# cd32_breakout_1_1a.net
KiCad netlist of a schematic drawn in EAGLE
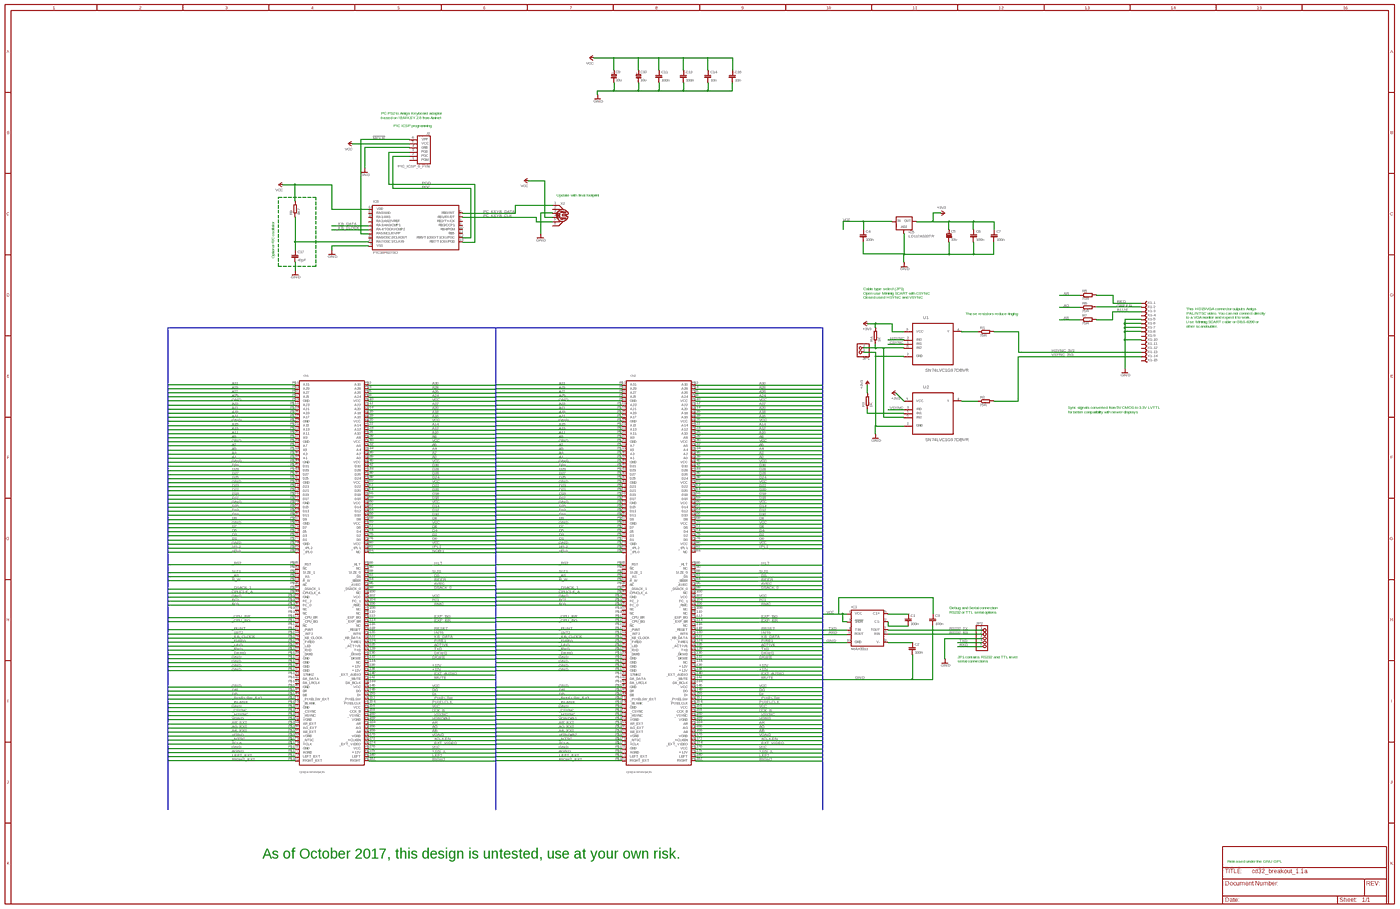
[diagram p0: schematic, sheet 1, overview]
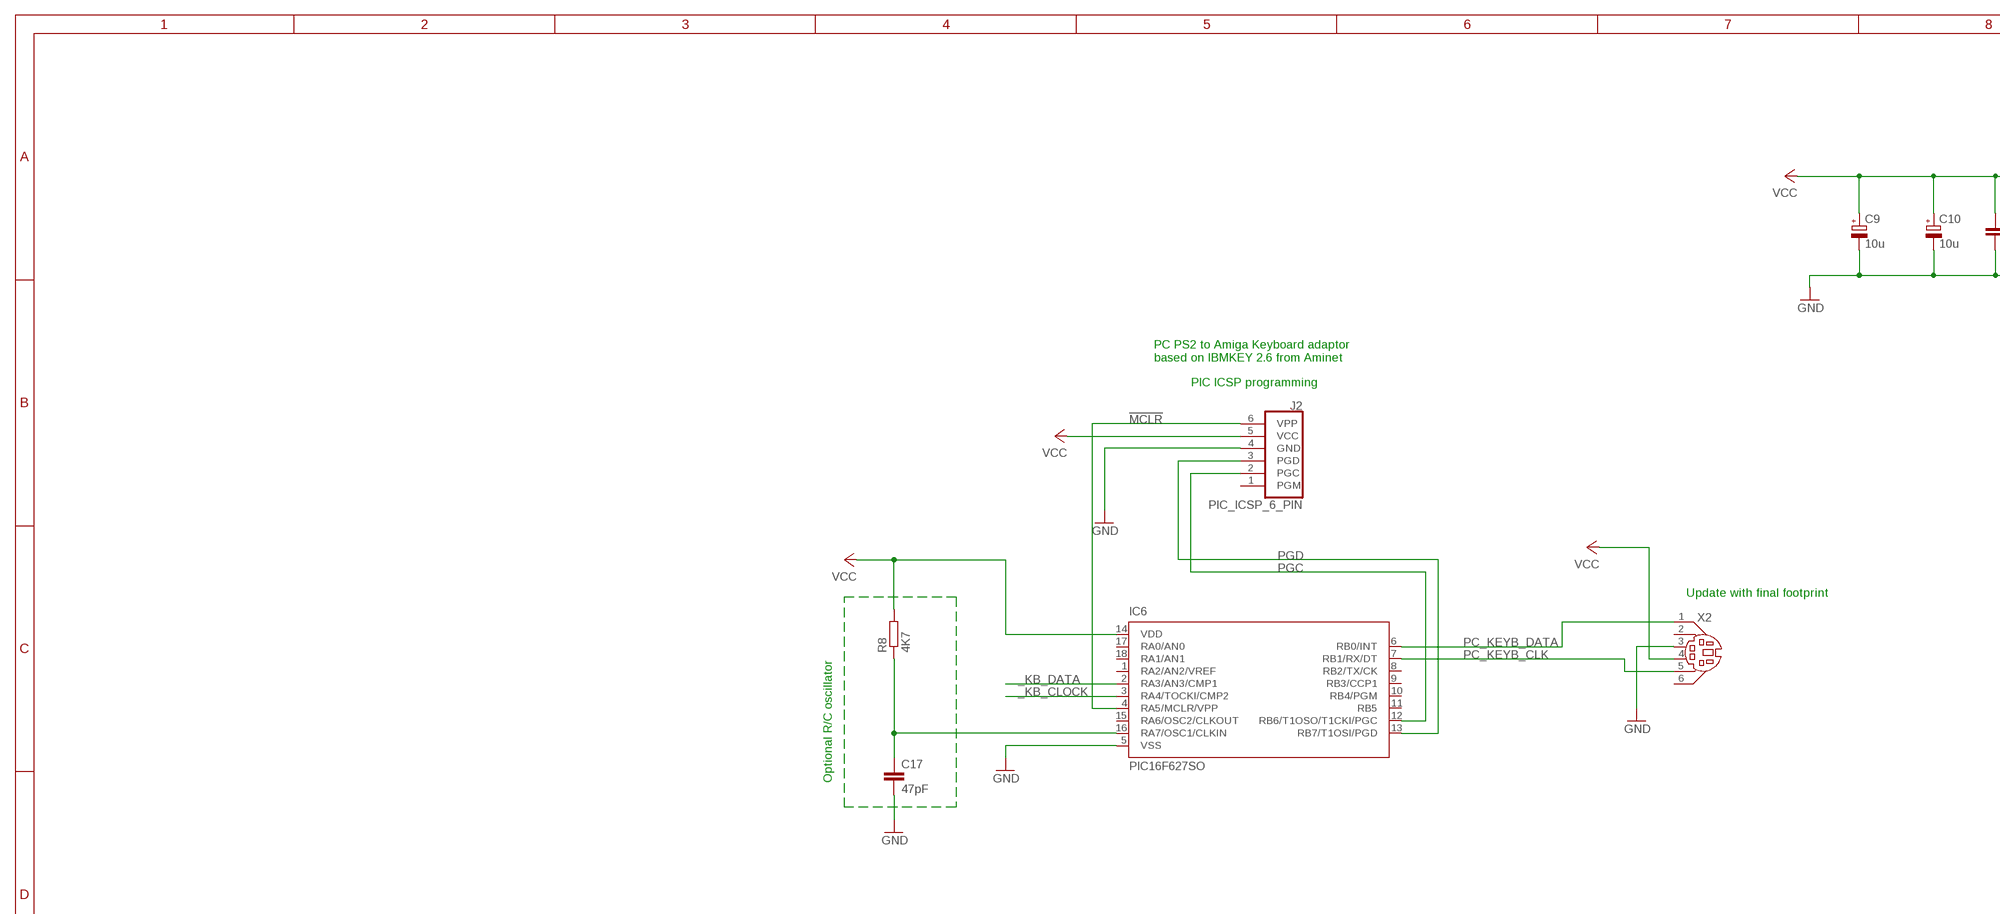
[diagram p1: schematic, sheet 1, part 1 of 4]
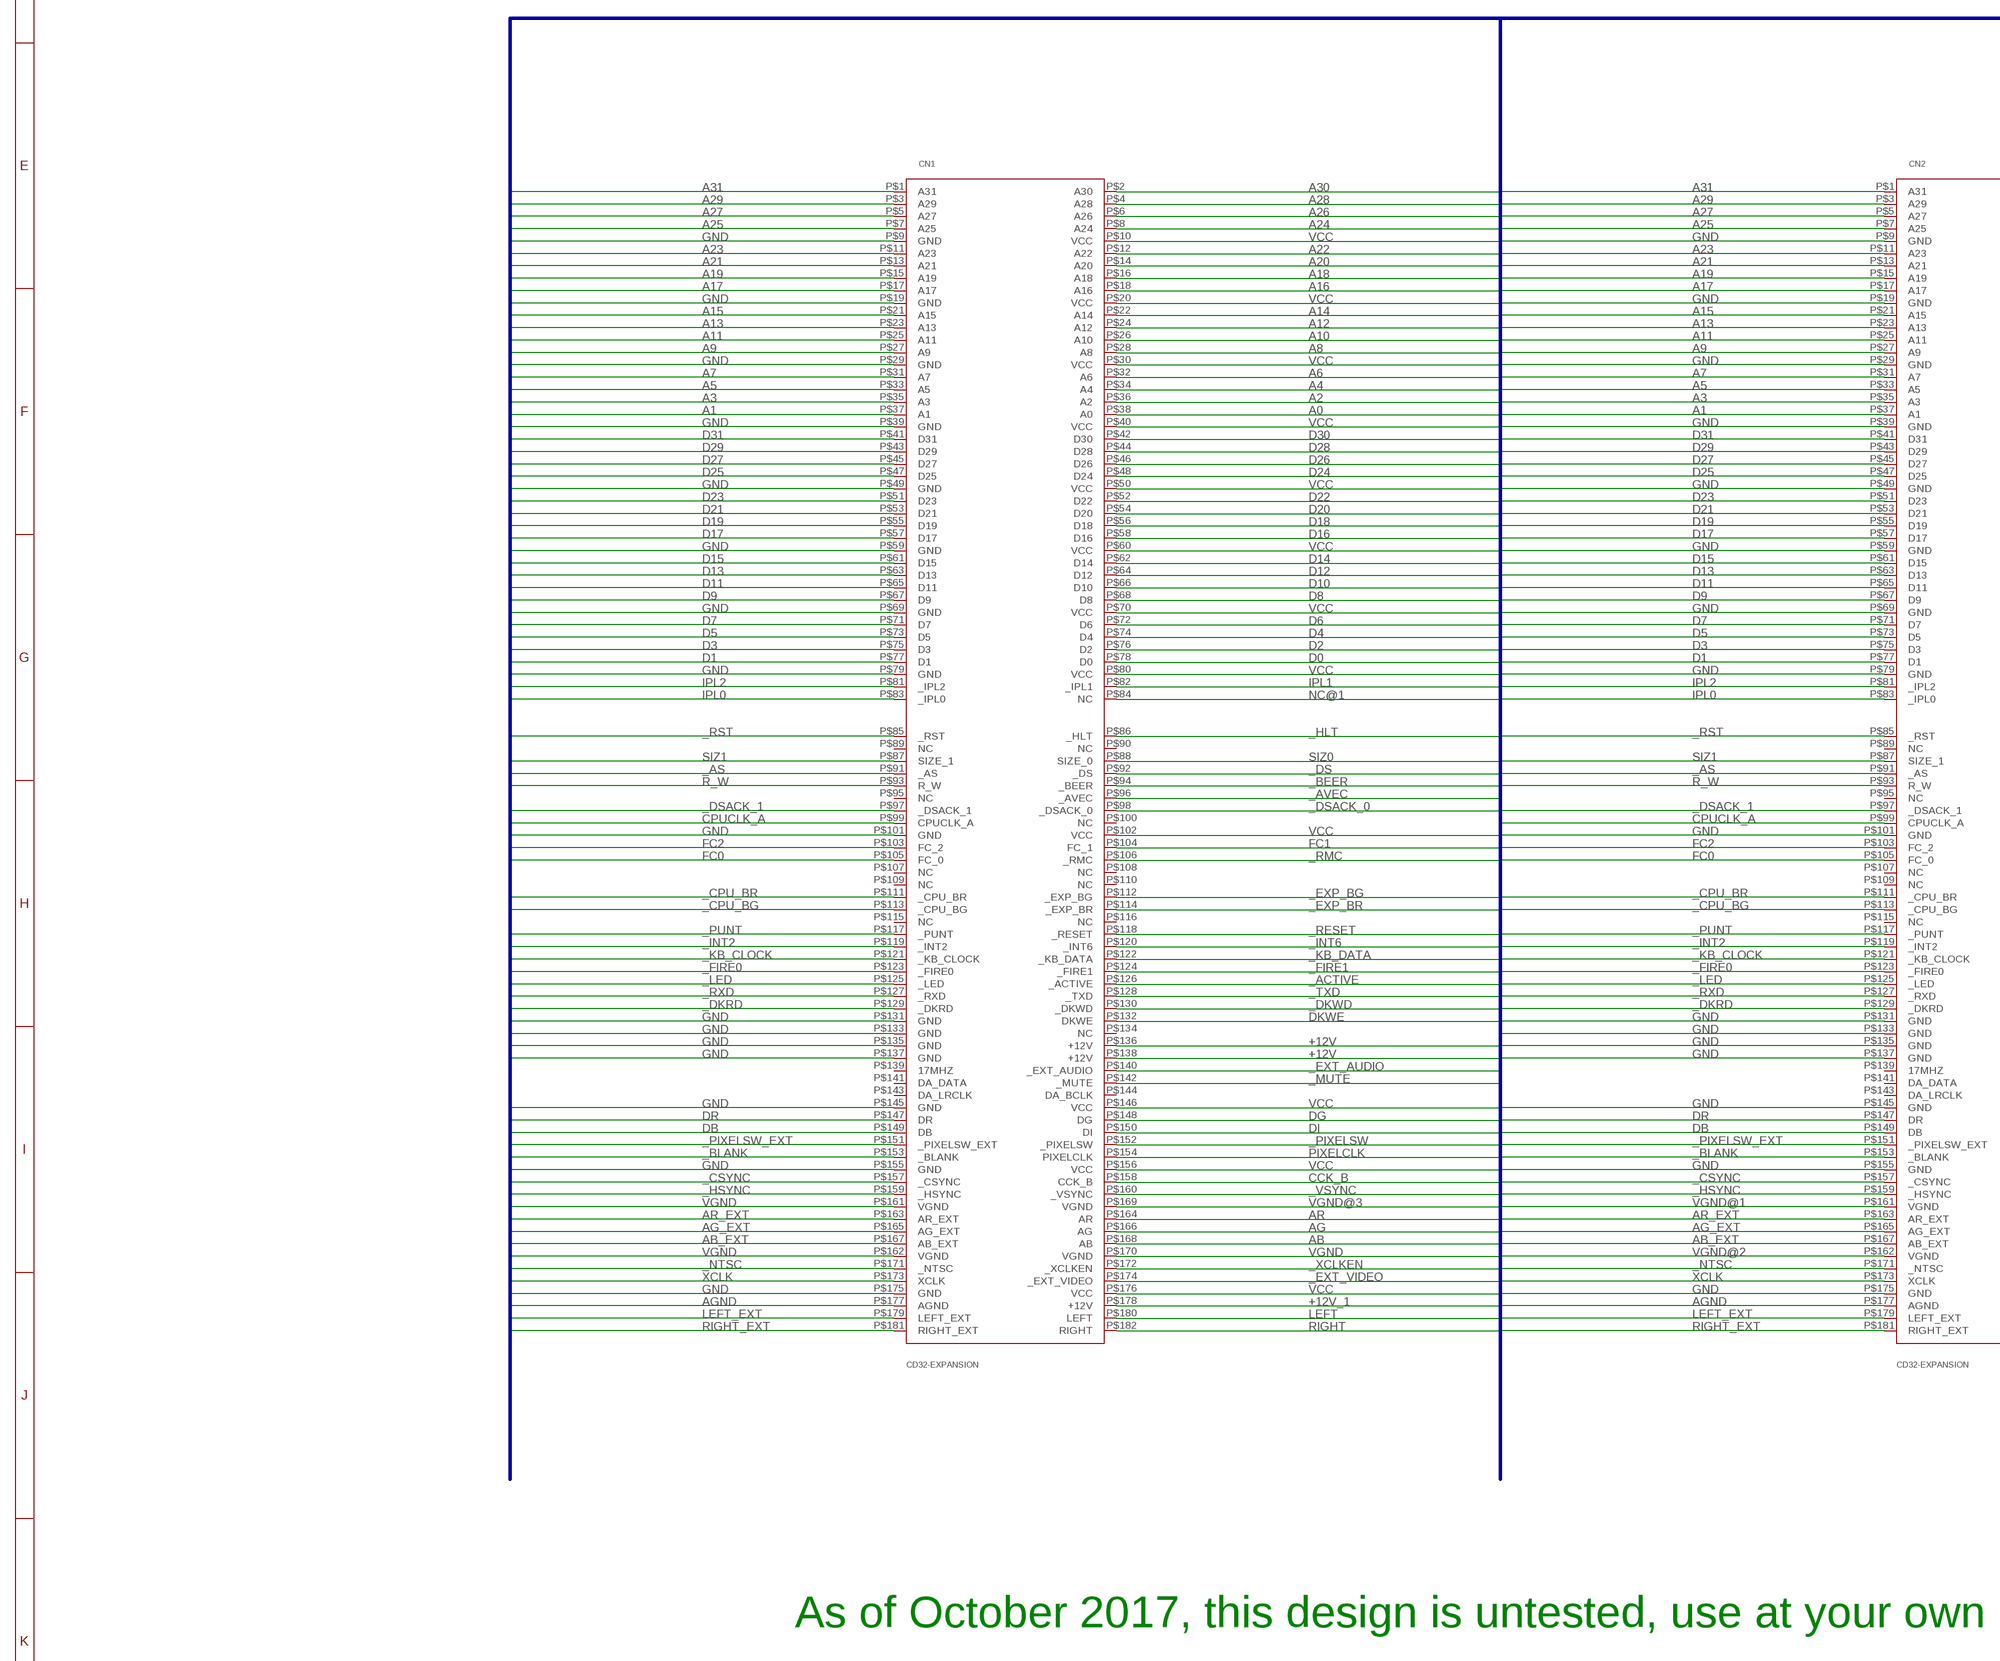
[diagram p2: schematic, sheet 1, part 2 of 4]
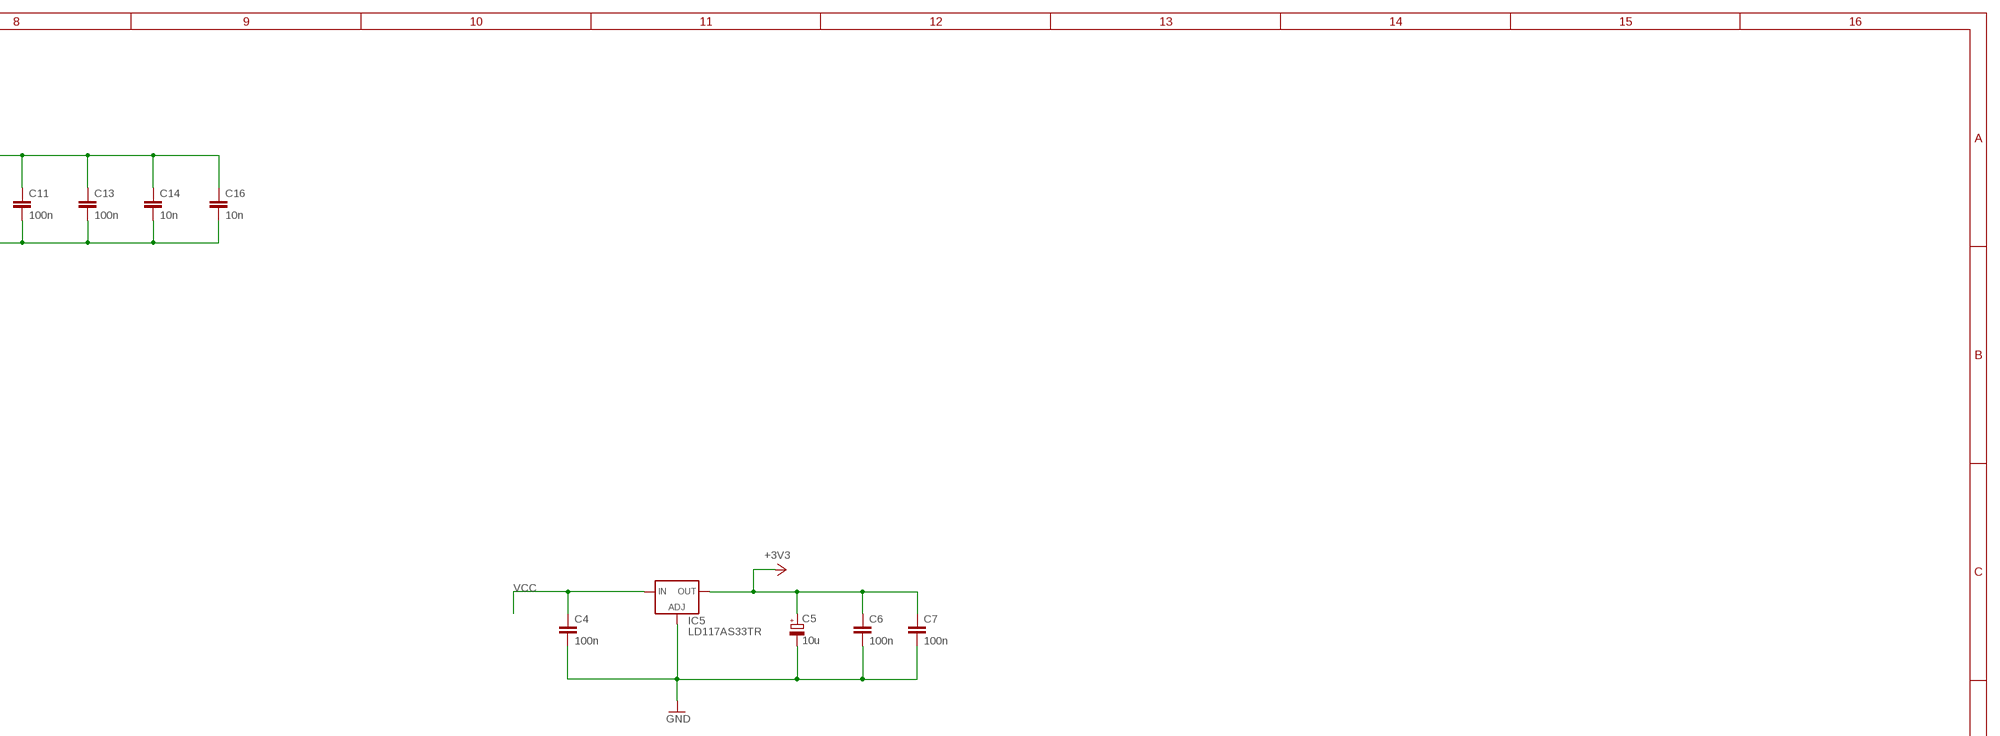
[diagram p3: schematic, sheet 1, part 3 of 4]
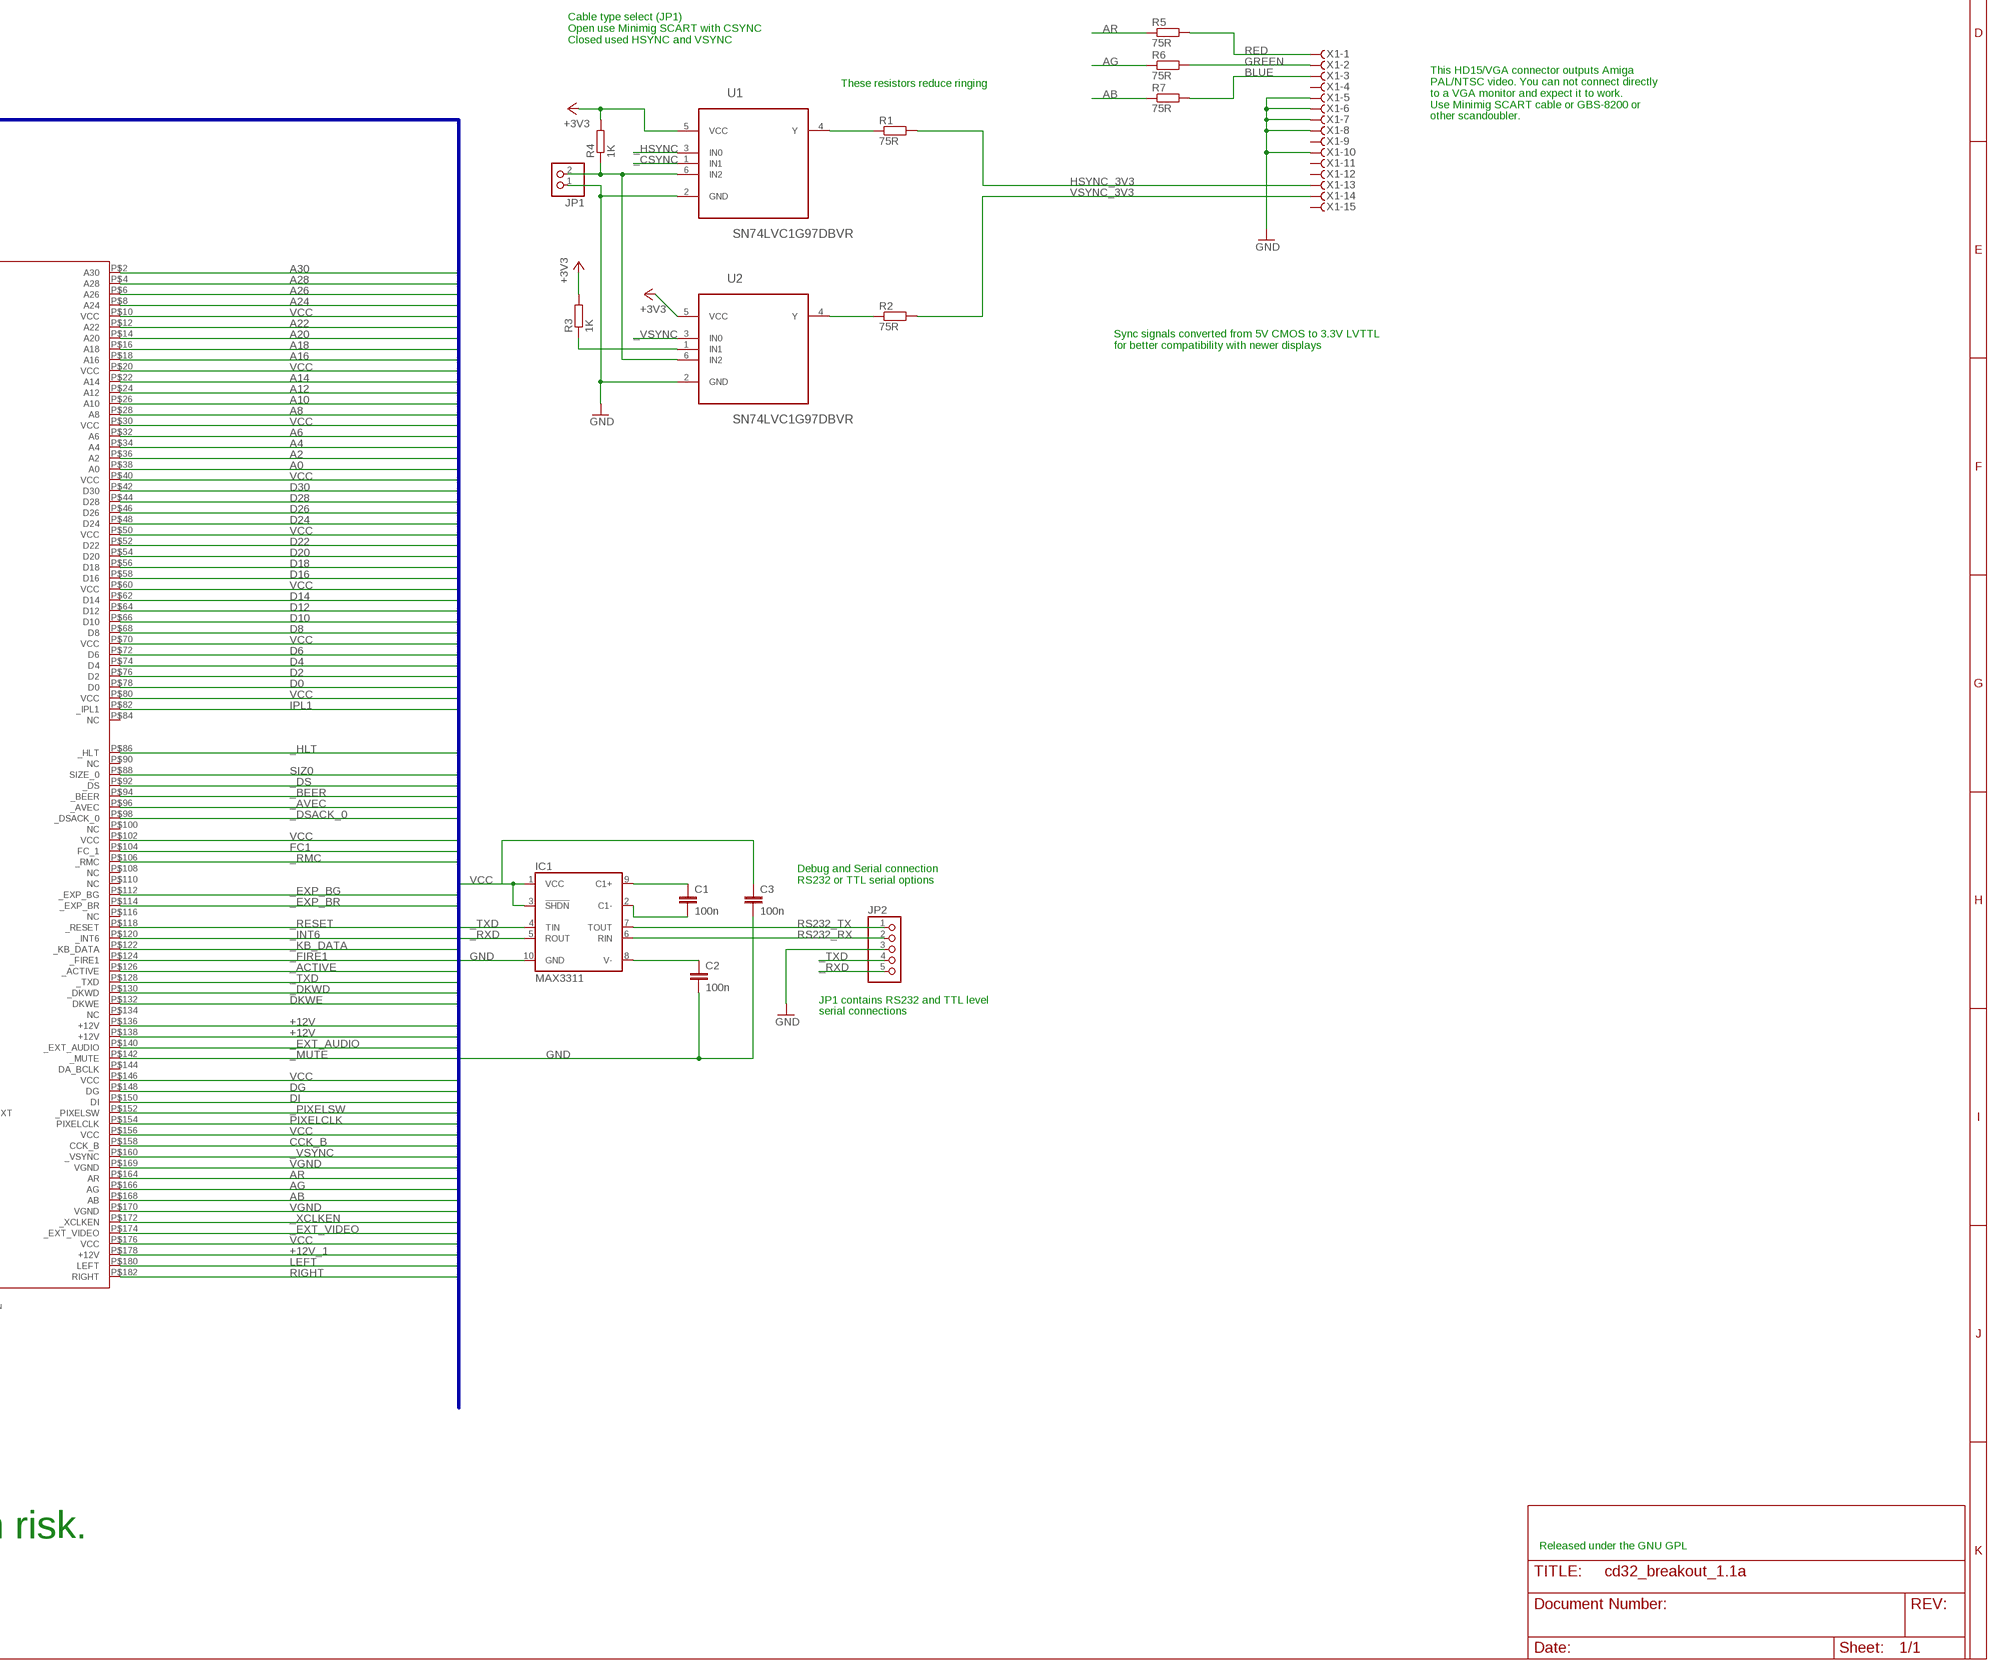
[diagram p4: schematic, sheet 1, part 4 of 4]

(export (version "E")
  (design (tool "Eeschema 10.0.6"))
  (components
    (comp (ref "C1")
      (value "100n")
      (footprint "eagle-import:C0603")
      (libsource (lib "eagle-import") (part "CC0603"))
    )
    (comp (ref "C2")
      (value "100n")
      (footprint "eagle-import:C0603")
      (libsource (lib "eagle-import") (part "CC0603"))
    )
    (comp (ref "C3")
      (value "100n")
      (footprint "eagle-import:C0603")
      (libsource (lib "eagle-import") (part "CC0603"))
    )
    (comp (ref "C4")
      (value "100n")
      (footprint "eagle-import:C0603")
      (libsource (lib "eagle-import") (part "C-EUC0603"))
    )
    (comp (ref "C5")
      (value "10u")
      (footprint "eagle-import:PANASONIC_C")
      (libsource (lib "eagle-import") (part "CPOL-EUC"))
    )
    (comp (ref "C6")
      (value "100n")
      (footprint "eagle-import:C0603")
      (libsource (lib "eagle-import") (part "C-EUC0603"))
    )
    (comp (ref "C7")
      (value "100n")
      (footprint "eagle-import:C0603")
      (libsource (lib "eagle-import") (part "C-EUC0603"))
    )
    (comp (ref "C9")
      (value "10u")
      (footprint "eagle-import:PANASONIC_C")
      (libsource (lib "eagle-import") (part "CPOL-EUC"))
    )
    (comp (ref "C10")
      (value "10u")
      (footprint "eagle-import:PANASONIC_C")
      (libsource (lib "eagle-import") (part "CPOL-EUC"))
    )
    (comp (ref "C11")
      (value "100n")
      (footprint "eagle-import:C0603")
      (libsource (lib "eagle-import") (part "C-EUC0603"))
    )
    (comp (ref "C13")
      (value "100n")
      (footprint "eagle-import:C0603")
      (libsource (lib "eagle-import") (part "C-EUC0603"))
    )
    (comp (ref "C14")
      (value "10n")
      (footprint "eagle-import:C0603")
      (libsource (lib "eagle-import") (part "C-EUC0603"))
    )
    (comp (ref "C16")
      (value "10n")
      (footprint "eagle-import:C0603")
      (libsource (lib "eagle-import") (part "C-EUC0603"))
    )
    (comp (ref "C17")
      (value "47pF")
      (footprint "eagle-import:C0603")
      (libsource (lib "eagle-import") (part "C-EUC0603"))
    )
    (comp (ref "CN1")
      (value "CD32-EXPANSION")
      (footprint "eagle-import:CD32_EXPANSION_182_MCA")
      (libsource (lib "eagle-import") (part "CD32-EXPANSION"))
    )
    (comp (ref "CN2")
      (value "CD32-EXPANSION")
      (footprint "eagle-import:CD32_EXPANSION_182_MCA")
      (libsource (lib "eagle-import") (part "CD32-EXPANSION"))
    )
    (comp (ref "IC1")
      (value "MAX3311")
      (footprint "eagle-import:UMAX10")
      (fields (field (name "MF") "MAXIM") (field (name "MPN") "MAX3311ECUB+"))
      (libsource (lib "eagle-import") (part "MAX3311"))
    )
    (comp (ref "IC5")
      (value "LD117AS33TR")
      (footprint "eagle-import:SOT223")
      (libsource (lib "eagle-import") (part "LD117A?S33TR"))
    )
    (comp (ref "IC6")
      (value "PIC16F627SO")
      (footprint "eagle-import:SO-18W")
      (fields (field (name "MF") "MICROCHIP") (field (name "MPN") "PIC16F627-04I/SO"))
      (libsource (lib "eagle-import") (part "PIC16F62SO7"))
    )
    (comp (ref "J2")
      (value "PIC_ICSP_6_PIN")
      (footprint "eagle-import:MOLEX-1X6")
      (libsource (lib "eagle-import") (part "PIC_ICSP_6_PIN"))
    )
    (comp (ref "JP1")
      (value "PINHD-1X2")
      (footprint "eagle-import:1X02")
      (libsource (lib "eagle-import") (part "PINHD-1X2"))
    )
    (comp (ref "JP2")
      (value "PINHD-1X5")
      (footprint "eagle-import:1X05")
      (libsource (lib "eagle-import") (part "PINHD-1X5"))
    )
    (comp (ref "R1")
      (value "75R")
      (footprint "eagle-import:R0603")
      (libsource (lib "eagle-import") (part "R-EU_R0603"))
    )
    (comp (ref "R2")
      (value "75R")
      (footprint "eagle-import:R0603")
      (libsource (lib "eagle-import") (part "R-EU_R0603"))
    )
    (comp (ref "R3")
      (value "1K")
      (footprint "eagle-import:R0603")
      (libsource (lib "eagle-import") (part "R-EU_R0603"))
    )
    (comp (ref "R4")
      (value "1K")
      (footprint "eagle-import:R0603")
      (libsource (lib "eagle-import") (part "R-EU_R0603"))
    )
    (comp (ref "R5")
      (value "75R")
      (footprint "eagle-import:R0603")
      (libsource (lib "eagle-import") (part "R-EU_R0603"))
    )
    (comp (ref "R6")
      (value "75R")
      (footprint "eagle-import:R0603")
      (libsource (lib "eagle-import") (part "R-EU_R0603"))
    )
    (comp (ref "R7")
      (value "75R")
      (footprint "eagle-import:R0603")
      (libsource (lib "eagle-import") (part "R-EU_R0603"))
    )
    (comp (ref "R8")
      (value "4K7")
      (footprint "eagle-import:R0603")
      (libsource (lib "eagle-import") (part "R-EU_R0603"))
    )
    (comp (ref "U1")
      (value "SN74LVC1G97DBVR")
      (footprint "eagle-import:SOT95P280X145-6N")
      (libsource (lib "eagle-import") (part "SN74LVC1G97DBVR"))
    )
    (comp (ref "U2")
      (value "SN74LVC1G97DBVR")
      (footprint "eagle-import:SOT95P280X145-6N")
      (libsource (lib "eagle-import") (part "SN74LVC1G97DBVR"))
    )
    (comp (ref "X1")
      (value "F15HDVS")
      (footprint "eagle-import:HDF15V")
      (libsource (lib "eagle-import") (part "F15?SHDV"))
    )
    (comp (ref "X2")
      (value "MDIN06K")
      (footprint "eagle-import:MDIN06K")
      (libsource (lib "eagle-import") (part "MDIN06K"))
    )
  )
  (nets
    (net (code "1") (name "+3V3") (class "Default")
      (node (ref "C5") (pin "+") (pinfunction "+_+") (pintype "passive"))
      (node (ref "C6") (pin "1") (pinfunction "1_1") (pintype "passive"))
      (node (ref "C7") (pin "1") (pinfunction "1_1") (pintype "passive"))
      (node (ref "IC5") (pin "4") (pinfunction "OUT_4") (pintype "passive"))
      (node (ref "R3") (pin "2") (pinfunction "2_2") (pintype "passive"))
      (node (ref "R4") (pin "2") (pinfunction "2_2") (pintype "passive"))
      (node (ref "U1") (pin "5") (pinfunction "VCC_5") (pintype "power_in"))
      (node (ref "U2") (pin "5") (pinfunction "VCC_5") (pintype "power_in"))
    )
    (net (code "2") (name "/+12V") (class "Default")
      (node (ref "CN1") (pin "P$136") (pinfunction "+12V_P$136") (pintype "bidirectional"))
      (node (ref "CN1") (pin "P$138") (pinfunction "+12V_P$138") (pintype "bidirectional"))
      (node (ref "CN2") (pin "P$136") (pinfunction "+12V_P$136") (pintype "bidirectional"))
      (node (ref "CN2") (pin "P$138") (pinfunction "+12V_P$138") (pintype "bidirectional"))
    )
    (net (code "3") (name "/+12V_1") (class "Default")
      (node (ref "CN1") (pin "P$178") (pinfunction "+12V_P$178") (pintype "bidirectional"))
      (node (ref "CN2") (pin "P$178") (pinfunction "+12V_P$178") (pintype "bidirectional"))
    )
    (net (code "4") (name "/A0") (class "Default")
      (node (ref "CN1") (pin "P$38") (pinfunction "A0_P$38") (pintype "bidirectional"))
      (node (ref "CN2") (pin "P$38") (pinfunction "A0_P$38") (pintype "bidirectional"))
    )
    (net (code "5") (name "/A1") (class "Default")
      (node (ref "CN1") (pin "P$37") (pinfunction "A1_P$37") (pintype "bidirectional"))
      (node (ref "CN2") (pin "P$37") (pinfunction "A1_P$37") (pintype "bidirectional"))
    )
    (net (code "6") (name "/A2") (class "Default")
      (node (ref "CN1") (pin "P$36") (pinfunction "A2_P$36") (pintype "bidirectional"))
      (node (ref "CN2") (pin "P$36") (pinfunction "A2_P$36") (pintype "bidirectional"))
    )
    (net (code "7") (name "/A3") (class "Default")
      (node (ref "CN1") (pin "P$35") (pinfunction "A3_P$35") (pintype "bidirectional"))
      (node (ref "CN2") (pin "P$35") (pinfunction "A3_P$35") (pintype "bidirectional"))
    )
    (net (code "8") (name "/A4") (class "Default")
      (node (ref "CN1") (pin "P$34") (pinfunction "A4_P$34") (pintype "bidirectional"))
      (node (ref "CN2") (pin "P$34") (pinfunction "A4_P$34") (pintype "bidirectional"))
    )
    (net (code "9") (name "/A5") (class "Default")
      (node (ref "CN1") (pin "P$33") (pinfunction "A5_P$33") (pintype "bidirectional"))
      (node (ref "CN2") (pin "P$33") (pinfunction "A5_P$33") (pintype "bidirectional"))
    )
    (net (code "10") (name "/A6") (class "Default")
      (node (ref "CN1") (pin "P$32") (pinfunction "A6_P$32") (pintype "bidirectional"))
      (node (ref "CN2") (pin "P$32") (pinfunction "A6_P$32") (pintype "bidirectional"))
    )
    (net (code "11") (name "/A7") (class "Default")
      (node (ref "CN1") (pin "P$31") (pinfunction "A7_P$31") (pintype "bidirectional"))
      (node (ref "CN2") (pin "P$31") (pinfunction "A7_P$31") (pintype "bidirectional"))
    )
    (net (code "12") (name "/A8") (class "Default")
      (node (ref "CN1") (pin "P$28") (pinfunction "A8_P$28") (pintype "bidirectional"))
      (node (ref "CN2") (pin "P$28") (pinfunction "A8_P$28") (pintype "bidirectional"))
    )
    (net (code "13") (name "/A9") (class "Default")
      (node (ref "CN1") (pin "P$27") (pinfunction "A9_P$27") (pintype "bidirectional"))
      (node (ref "CN2") (pin "P$27") (pinfunction "A9_P$27") (pintype "bidirectional"))
    )
    (net (code "14") (name "/A10") (class "Default")
      (node (ref "CN1") (pin "P$26") (pinfunction "A10_P$26") (pintype "bidirectional"))
      (node (ref "CN2") (pin "P$26") (pinfunction "A10_P$26") (pintype "bidirectional"))
    )
    (net (code "15") (name "/A11") (class "Default")
      (node (ref "CN1") (pin "P$25") (pinfunction "A11_P$25") (pintype "bidirectional"))
      (node (ref "CN2") (pin "P$25") (pinfunction "A11_P$25") (pintype "bidirectional"))
    )
    (net (code "16") (name "/A12") (class "Default")
      (node (ref "CN1") (pin "P$24") (pinfunction "A12_P$24") (pintype "bidirectional"))
      (node (ref "CN2") (pin "P$24") (pinfunction "A12_P$24") (pintype "bidirectional"))
    )
    (net (code "17") (name "/A13") (class "Default")
      (node (ref "CN1") (pin "P$23") (pinfunction "A13_P$23") (pintype "bidirectional"))
      (node (ref "CN2") (pin "P$23") (pinfunction "A13_P$23") (pintype "bidirectional"))
    )
    (net (code "18") (name "/A14") (class "Default")
      (node (ref "CN1") (pin "P$22") (pinfunction "A14_P$22") (pintype "bidirectional"))
      (node (ref "CN2") (pin "P$22") (pinfunction "A14_P$22") (pintype "bidirectional"))
    )
    (net (code "19") (name "/A15") (class "Default")
      (node (ref "CN1") (pin "P$21") (pinfunction "A15_P$21") (pintype "bidirectional"))
      (node (ref "CN2") (pin "P$21") (pinfunction "A15_P$21") (pintype "bidirectional"))
    )
    (net (code "20") (name "/A16") (class "Default")
      (node (ref "CN1") (pin "P$18") (pinfunction "A16_P$18") (pintype "bidirectional"))
      (node (ref "CN2") (pin "P$18") (pinfunction "A16_P$18") (pintype "bidirectional"))
    )
    (net (code "21") (name "/A17") (class "Default")
      (node (ref "CN1") (pin "P$17") (pinfunction "A17_P$17") (pintype "bidirectional"))
      (node (ref "CN2") (pin "P$17") (pinfunction "A17_P$17") (pintype "bidirectional"))
    )
    (net (code "22") (name "/A18") (class "Default")
      (node (ref "CN1") (pin "P$16") (pinfunction "A18_P$16") (pintype "bidirectional"))
      (node (ref "CN2") (pin "P$16") (pinfunction "A18_P$16") (pintype "bidirectional"))
    )
    (net (code "23") (name "/A19") (class "Default")
      (node (ref "CN1") (pin "P$15") (pinfunction "A19_P$15") (pintype "bidirectional"))
      (node (ref "CN2") (pin "P$15") (pinfunction "A19_P$15") (pintype "bidirectional"))
    )
    (net (code "24") (name "/A20") (class "Default")
      (node (ref "CN1") (pin "P$14") (pinfunction "A20_P$14") (pintype "bidirectional"))
      (node (ref "CN2") (pin "P$14") (pinfunction "A20_P$14") (pintype "bidirectional"))
    )
    (net (code "25") (name "/A21") (class "Default")
      (node (ref "CN1") (pin "P$13") (pinfunction "A21_P$13") (pintype "bidirectional"))
      (node (ref "CN2") (pin "P$13") (pinfunction "A21_P$13") (pintype "bidirectional"))
    )
    (net (code "26") (name "/A22") (class "Default")
      (node (ref "CN1") (pin "P$12") (pinfunction "A22_P$12") (pintype "bidirectional"))
      (node (ref "CN2") (pin "P$12") (pinfunction "A22_P$12") (pintype "bidirectional"))
    )
    (net (code "27") (name "/A23") (class "Default")
      (node (ref "CN1") (pin "P$11") (pinfunction "A23_P$11") (pintype "bidirectional"))
      (node (ref "CN2") (pin "P$11") (pinfunction "A23_P$11") (pintype "bidirectional"))
    )
    (net (code "28") (name "/A24") (class "Default")
      (node (ref "CN1") (pin "P$8") (pinfunction "A24_P$8") (pintype "bidirectional"))
      (node (ref "CN2") (pin "P$8") (pinfunction "A24_P$8") (pintype "bidirectional"))
    )
    (net (code "29") (name "/A25") (class "Default")
      (node (ref "CN1") (pin "P$7") (pinfunction "A25_P$7") (pintype "bidirectional"))
      (node (ref "CN2") (pin "P$7") (pinfunction "A25_P$7") (pintype "bidirectional"))
    )
    (net (code "30") (name "/A26") (class "Default")
      (node (ref "CN1") (pin "P$6") (pinfunction "A26_P$6") (pintype "bidirectional"))
      (node (ref "CN2") (pin "P$6") (pinfunction "A26_P$6") (pintype "bidirectional"))
    )
    (net (code "31") (name "/A27") (class "Default")
      (node (ref "CN1") (pin "P$5") (pinfunction "A27_P$5") (pintype "bidirectional"))
      (node (ref "CN2") (pin "P$5") (pinfunction "A27_P$5") (pintype "bidirectional"))
    )
    (net (code "32") (name "/A28") (class "Default")
      (node (ref "CN1") (pin "P$4") (pinfunction "A28_P$4") (pintype "bidirectional"))
      (node (ref "CN2") (pin "P$4") (pinfunction "A28_P$4") (pintype "bidirectional"))
    )
    (net (code "33") (name "/A29") (class "Default")
      (node (ref "CN1") (pin "P$3") (pinfunction "A29_P$3") (pintype "bidirectional"))
      (node (ref "CN2") (pin "P$3") (pinfunction "A29_P$3") (pintype "bidirectional"))
    )
    (net (code "34") (name "/A30") (class "Default")
      (node (ref "CN1") (pin "P$2") (pinfunction "A30_P$2") (pintype "bidirectional"))
      (node (ref "CN2") (pin "P$2") (pinfunction "A30_P$2") (pintype "bidirectional"))
    )
    (net (code "35") (name "/A31") (class "Default")
      (node (ref "CN1") (pin "P$1") (pinfunction "A31_P$1") (pintype "bidirectional"))
      (node (ref "CN2") (pin "P$1") (pinfunction "A31_P$1") (pintype "bidirectional"))
    )
    (net (code "36") (name "/AB") (class "Default")
      (node (ref "CN1") (pin "P$168") (pinfunction "AB_P$168") (pintype "bidirectional"))
      (node (ref "CN2") (pin "P$168") (pinfunction "AB_P$168") (pintype "bidirectional"))
      (node (ref "R7") (pin "1") (pinfunction "1_1") (pintype "passive"))
    )
    (net (code "37") (name "/AB_EXT") (class "Default")
      (node (ref "CN1") (pin "P$167") (pinfunction "AB_EXT_P$167") (pintype "bidirectional"))
      (node (ref "CN2") (pin "P$167") (pinfunction "AB_EXT_P$167") (pintype "bidirectional"))
    )
    (net (code "38") (name "/AG") (class "Default")
      (node (ref "CN1") (pin "P$166") (pinfunction "AG_P$166") (pintype "bidirectional"))
      (node (ref "CN2") (pin "P$166") (pinfunction "AG_P$166") (pintype "bidirectional"))
      (node (ref "R6") (pin "1") (pinfunction "1_1") (pintype "passive"))
    )
    (net (code "39") (name "/AGND") (class "Default")
      (node (ref "CN1") (pin "P$177") (pinfunction "AGND_P$177") (pintype "bidirectional"))
      (node (ref "CN2") (pin "P$177") (pinfunction "AGND_P$177") (pintype "bidirectional"))
    )
    (net (code "40") (name "/AG_EXT") (class "Default")
      (node (ref "CN1") (pin "P$165") (pinfunction "AG_EXT_P$165") (pintype "bidirectional"))
      (node (ref "CN2") (pin "P$165") (pinfunction "AG_EXT_P$165") (pintype "bidirectional"))
    )
    (net (code "41") (name "/AR") (class "Default")
      (node (ref "CN1") (pin "P$164") (pinfunction "AR_P$164") (pintype "bidirectional"))
      (node (ref "CN2") (pin "P$164") (pinfunction "AR_P$164") (pintype "bidirectional"))
      (node (ref "R5") (pin "1") (pinfunction "1_1") (pintype "passive"))
    )
    (net (code "42") (name "/AR_EXT") (class "Default")
      (node (ref "CN1") (pin "P$163") (pinfunction "AR_EXT_P$163") (pintype "bidirectional"))
      (node (ref "CN2") (pin "P$163") (pinfunction "AR_EXT_P$163") (pintype "bidirectional"))
    )
    (net (code "43") (name "/BLUE") (class "Default")
      (node (ref "R7") (pin "2") (pinfunction "2_2") (pintype "passive"))
      (node (ref "X1") (pin "3") (pinfunction "F_3") (pintype "passive"))
    )
    (net (code "44") (name "/CCK_B") (class "Default")
      (node (ref "CN1") (pin "P$158") (pinfunction "CCK_B_P$158") (pintype "bidirectional"))
      (node (ref "CN2") (pin "P$158") (pinfunction "CCK_B_P$158") (pintype "bidirectional"))
    )
    (net (code "45") (name "/CPUCLK_A") (class "Default")
      (node (ref "CN1") (pin "P$99") (pinfunction "CPUCLK_A_P$99") (pintype "bidirectional"))
      (node (ref "CN2") (pin "P$99") (pinfunction "CPUCLK_A_P$99") (pintype "bidirectional"))
    )
    (net (code "46") (name "/D0") (class "Default")
      (node (ref "CN1") (pin "P$78") (pinfunction "D0_P$78") (pintype "bidirectional"))
      (node (ref "CN2") (pin "P$78") (pinfunction "D0_P$78") (pintype "bidirectional"))
    )
    (net (code "47") (name "/D1") (class "Default")
      (node (ref "CN1") (pin "P$77") (pinfunction "D1_P$77") (pintype "bidirectional"))
      (node (ref "CN2") (pin "P$77") (pinfunction "D1_P$77") (pintype "bidirectional"))
    )
    (net (code "48") (name "/D2") (class "Default")
      (node (ref "CN1") (pin "P$76") (pinfunction "D2_P$76") (pintype "bidirectional"))
      (node (ref "CN2") (pin "P$76") (pinfunction "D2_P$76") (pintype "bidirectional"))
    )
    (net (code "49") (name "/D3") (class "Default")
      (node (ref "CN1") (pin "P$75") (pinfunction "D3_P$75") (pintype "bidirectional"))
      (node (ref "CN2") (pin "P$75") (pinfunction "D3_P$75") (pintype "bidirectional"))
    )
    (net (code "50") (name "/D4") (class "Default")
      (node (ref "CN1") (pin "P$74") (pinfunction "D4_P$74") (pintype "bidirectional"))
      (node (ref "CN2") (pin "P$74") (pinfunction "D4_P$74") (pintype "bidirectional"))
    )
    (net (code "51") (name "/D5") (class "Default")
      (node (ref "CN1") (pin "P$73") (pinfunction "D5_P$73") (pintype "bidirectional"))
      (node (ref "CN2") (pin "P$73") (pinfunction "D5_P$73") (pintype "bidirectional"))
    )
    (net (code "52") (name "/D6") (class "Default")
      (node (ref "CN1") (pin "P$72") (pinfunction "D6_P$72") (pintype "bidirectional"))
      (node (ref "CN2") (pin "P$72") (pinfunction "D6_P$72") (pintype "bidirectional"))
    )
    (net (code "53") (name "/D7") (class "Default")
      (node (ref "CN1") (pin "P$71") (pinfunction "D7_P$71") (pintype "bidirectional"))
      (node (ref "CN2") (pin "P$71") (pinfunction "D7_P$71") (pintype "bidirectional"))
    )
    (net (code "54") (name "/D8") (class "Default")
      (node (ref "CN1") (pin "P$68") (pinfunction "D8_P$68") (pintype "bidirectional"))
      (node (ref "CN2") (pin "P$68") (pinfunction "D8_P$68") (pintype "bidirectional"))
    )
    (net (code "55") (name "/D9") (class "Default")
      (node (ref "CN1") (pin "P$67") (pinfunction "D9_P$67") (pintype "bidirectional"))
      (node (ref "CN2") (pin "P$67") (pinfunction "D9_P$67") (pintype "bidirectional"))
    )
    (net (code "56") (name "/D10") (class "Default")
      (node (ref "CN1") (pin "P$66") (pinfunction "D10_P$66") (pintype "bidirectional"))
      (node (ref "CN2") (pin "P$66") (pinfunction "D10_P$66") (pintype "bidirectional"))
    )
    (net (code "57") (name "/D11") (class "Default")
      (node (ref "CN1") (pin "P$65") (pinfunction "D11_P$65") (pintype "bidirectional"))
      (node (ref "CN2") (pin "P$65") (pinfunction "D11_P$65") (pintype "bidirectional"))
    )
    (net (code "58") (name "/D12") (class "Default")
      (node (ref "CN1") (pin "P$64") (pinfunction "D12_P$64") (pintype "bidirectional"))
      (node (ref "CN2") (pin "P$64") (pinfunction "D12_P$64") (pintype "bidirectional"))
    )
    (net (code "59") (name "/D13") (class "Default")
      (node (ref "CN1") (pin "P$63") (pinfunction "D13_P$63") (pintype "bidirectional"))
      (node (ref "CN2") (pin "P$63") (pinfunction "D13_P$63") (pintype "bidirectional"))
    )
    (net (code "60") (name "/D14") (class "Default")
      (node (ref "CN1") (pin "P$62") (pinfunction "D14_P$62") (pintype "bidirectional"))
      (node (ref "CN2") (pin "P$62") (pinfunction "D14_P$62") (pintype "bidirectional"))
    )
    (net (code "61") (name "/D15") (class "Default")
      (node (ref "CN1") (pin "P$61") (pinfunction "D15_P$61") (pintype "bidirectional"))
      (node (ref "CN2") (pin "P$61") (pinfunction "D15_P$61") (pintype "bidirectional"))
    )
    (net (code "62") (name "/D16") (class "Default")
      (node (ref "CN1") (pin "P$58") (pinfunction "D16_P$58") (pintype "bidirectional"))
      (node (ref "CN2") (pin "P$58") (pinfunction "D16_P$58") (pintype "bidirectional"))
    )
    (net (code "63") (name "/D17") (class "Default")
      (node (ref "CN1") (pin "P$57") (pinfunction "D17_P$57") (pintype "bidirectional"))
      (node (ref "CN2") (pin "P$57") (pinfunction "D17_P$57") (pintype "bidirectional"))
    )
    (net (code "64") (name "/D18") (class "Default")
      (node (ref "CN1") (pin "P$56") (pinfunction "D18_P$56") (pintype "bidirectional"))
      (node (ref "CN2") (pin "P$56") (pinfunction "D18_P$56") (pintype "bidirectional"))
    )
    (net (code "65") (name "/D19") (class "Default")
      (node (ref "CN1") (pin "P$55") (pinfunction "D19_P$55") (pintype "bidirectional"))
      (node (ref "CN2") (pin "P$55") (pinfunction "D19_P$55") (pintype "bidirectional"))
    )
    (net (code "66") (name "/D20") (class "Default")
      (node (ref "CN1") (pin "P$54") (pinfunction "D20_P$54") (pintype "bidirectional"))
      (node (ref "CN2") (pin "P$54") (pinfunction "D20_P$54") (pintype "bidirectional"))
    )
    (net (code "67") (name "/D21") (class "Default")
      (node (ref "CN1") (pin "P$53") (pinfunction "D21_P$53") (pintype "bidirectional"))
      (node (ref "CN2") (pin "P$53") (pinfunction "D21_P$53") (pintype "bidirectional"))
    )
    (net (code "68") (name "/D22") (class "Default")
      (node (ref "CN1") (pin "P$52") (pinfunction "D22_P$52") (pintype "bidirectional"))
      (node (ref "CN2") (pin "P$52") (pinfunction "D22_P$52") (pintype "bidirectional"))
    )
    (net (code "69") (name "/D23") (class "Default")
      (node (ref "CN1") (pin "P$51") (pinfunction "D23_P$51") (pintype "bidirectional"))
      (node (ref "CN2") (pin "P$51") (pinfunction "D23_P$51") (pintype "bidirectional"))
    )
    (net (code "70") (name "/D24") (class "Default")
      (node (ref "CN1") (pin "P$48") (pinfunction "D24_P$48") (pintype "bidirectional"))
      (node (ref "CN2") (pin "P$48") (pinfunction "D24_P$48") (pintype "bidirectional"))
    )
    (net (code "71") (name "/D25") (class "Default")
      (node (ref "CN1") (pin "P$47") (pinfunction "D25_P$47") (pintype "bidirectional"))
      (node (ref "CN2") (pin "P$47") (pinfunction "D25_P$47") (pintype "bidirectional"))
    )
    (net (code "72") (name "/D26") (class "Default")
      (node (ref "CN1") (pin "P$46") (pinfunction "D26_P$46") (pintype "bidirectional"))
      (node (ref "CN2") (pin "P$46") (pinfunction "D26_P$46") (pintype "bidirectional"))
    )
    (net (code "73") (name "/D27") (class "Default")
      (node (ref "CN1") (pin "P$45") (pinfunction "D27_P$45") (pintype "bidirectional"))
      (node (ref "CN2") (pin "P$45") (pinfunction "D27_P$45") (pintype "bidirectional"))
    )
    (net (code "74") (name "/D28") (class "Default")
      (node (ref "CN1") (pin "P$44") (pinfunction "D28_P$44") (pintype "bidirectional"))
      (node (ref "CN2") (pin "P$44") (pinfunction "D28_P$44") (pintype "bidirectional"))
    )
    (net (code "75") (name "/D29") (class "Default")
      (node (ref "CN1") (pin "P$43") (pinfunction "D29_P$43") (pintype "bidirectional"))
      (node (ref "CN2") (pin "P$43") (pinfunction "D29_P$43") (pintype "bidirectional"))
    )
    (net (code "76") (name "/D30") (class "Default")
      (node (ref "CN1") (pin "P$42") (pinfunction "D30_P$42") (pintype "bidirectional"))
      (node (ref "CN2") (pin "P$42") (pinfunction "D30_P$42") (pintype "bidirectional"))
    )
    (net (code "77") (name "/D31") (class "Default")
      (node (ref "CN1") (pin "P$41") (pinfunction "D31_P$41") (pintype "bidirectional"))
      (node (ref "CN2") (pin "P$41") (pinfunction "D31_P$41") (pintype "bidirectional"))
    )
    (net (code "78") (name "/DB") (class "Default")
      (node (ref "CN1") (pin "P$149") (pinfunction "DB_P$149") (pintype "bidirectional"))
      (node (ref "CN2") (pin "P$149") (pinfunction "DB_P$149") (pintype "bidirectional"))
    )
    (net (code "79") (name "/DG") (class "Default")
      (node (ref "CN1") (pin "P$148") (pinfunction "DG_P$148") (pintype "bidirectional"))
      (node (ref "CN2") (pin "P$148") (pinfunction "DG_P$148") (pintype "bidirectional"))
    )
    (net (code "80") (name "/DI") (class "Default")
      (node (ref "CN1") (pin "P$150") (pinfunction "DI_P$150") (pintype "bidirectional"))
      (node (ref "CN2") (pin "P$150") (pinfunction "DI_P$150") (pintype "bidirectional"))
    )
    (net (code "81") (name "/DKWE") (class "Default")
      (node (ref "CN1") (pin "P$132") (pinfunction "DKWE_P$132") (pintype "bidirectional"))
      (node (ref "CN2") (pin "P$132") (pinfunction "DKWE_P$132") (pintype "bidirectional"))
    )
    (net (code "82") (name "/DR") (class "Default")
      (node (ref "CN1") (pin "P$147") (pinfunction "DR_P$147") (pintype "bidirectional"))
      (node (ref "CN2") (pin "P$147") (pinfunction "DR_P$147") (pintype "bidirectional"))
    )
    (net (code "83") (name "/FC0") (class "Default")
      (node (ref "CN1") (pin "P$105") (pinfunction "FC_0_P$105") (pintype "bidirectional"))
      (node (ref "CN2") (pin "P$105") (pinfunction "FC_0_P$105") (pintype "bidirectional"))
    )
    (net (code "84") (name "/FC1") (class "Default")
      (node (ref "CN1") (pin "P$104") (pinfunction "FC_1_P$104") (pintype "bidirectional"))
      (node (ref "CN2") (pin "P$104") (pinfunction "FC_1_P$104") (pintype "bidirectional"))
    )
    (net (code "85") (name "/FC2") (class "Default")
      (node (ref "CN1") (pin "P$103") (pinfunction "FC_2_P$103") (pintype "bidirectional"))
      (node (ref "CN2") (pin "P$103") (pinfunction "FC_2_P$103") (pintype "bidirectional"))
    )
    (net (code "86") (name "/GREEN") (class "Default")
      (node (ref "R6") (pin "2") (pinfunction "2_2") (pintype "passive"))
      (node (ref "X1") (pin "2") (pinfunction "F_2") (pintype "passive"))
    )
    (net (code "87") (name "/HSYNC_3V3") (class "Default")
      (node (ref "R1") (pin "2") (pinfunction "2_2") (pintype "passive"))
      (node (ref "X1") (pin "13") (pinfunction "F_13") (pintype "passive"))
    )
    (net (code "88") (name "/IPL0") (class "Default")
      (node (ref "CN1") (pin "P$83") (pinfunction "_IPL0_P$83") (pintype "bidirectional"))
      (node (ref "CN2") (pin "P$83") (pinfunction "_IPL0_P$83") (pintype "bidirectional"))
    )
    (net (code "89") (name "/IPL1") (class "Default")
      (node (ref "CN1") (pin "P$82") (pinfunction "_IPL1_P$82") (pintype "bidirectional"))
      (node (ref "CN2") (pin "P$82") (pinfunction "_IPL1_P$82") (pintype "bidirectional"))
    )
    (net (code "90") (name "/IPL2") (class "Default")
      (node (ref "CN1") (pin "P$81") (pinfunction "_IPL2_P$81") (pintype "bidirectional"))
      (node (ref "CN2") (pin "P$81") (pinfunction "_IPL2_P$81") (pintype "bidirectional"))
    )
    (net (code "91") (name "/LEFT") (class "Default")
      (node (ref "CN1") (pin "P$180") (pinfunction "LEFT_P$180") (pintype "bidirectional"))
      (node (ref "CN2") (pin "P$180") (pinfunction "LEFT_P$180") (pintype "bidirectional"))
    )
    (net (code "92") (name "/LEFT_EXT") (class "Default")
      (node (ref "CN1") (pin "P$179") (pinfunction "LEFT_EXT_P$179") (pintype "bidirectional"))
      (node (ref "CN2") (pin "P$179") (pinfunction "LEFT_EXT_P$179") (pintype "bidirectional"))
    )
    (net (code "93") (name "/NC@1") (class "Default")
      (node (ref "CN1") (pin "P$84") (pinfunction "NC_P$84") (pintype "bidirectional"))
    )
    (net (code "94") (name "/PC_KEYB_CLK") (class "Default")
      (node (ref "IC6") (pin "7") (pinfunction "RB1/RX/DT_7") (pintype "bidirectional"))
      (node (ref "X2") (pin "5") (pinfunction "5_5") (pintype "passive"))
    )
    (net (code "95") (name "/PC_KEYB_DATA") (class "Default")
      (node (ref "IC6") (pin "6") (pinfunction "RB0/INT_6") (pintype "bidirectional"))
      (node (ref "X2") (pin "1") (pinfunction "1_1") (pintype "passive"))
    )
    (net (code "96") (name "/PGC") (class "Default")
      (node (ref "IC6") (pin "12") (pinfunction "RB6/T1OSO/T1CKI/PGC_12") (pintype "bidirectional"))
      (node (ref "J2") (pin "2") (pinfunction "PGC_2") (pintype "bidirectional"))
    )
    (net (code "97") (name "/PGD") (class "Default")
      (node (ref "IC6") (pin "13") (pinfunction "RB7/T1OSI/PGD_13") (pintype "bidirectional"))
      (node (ref "J2") (pin "3") (pinfunction "PGD_3") (pintype "bidirectional"))
    )
    (net (code "98") (name "/PIXELCLK") (class "Default")
      (node (ref "CN1") (pin "P$154") (pinfunction "PIXELCLK_P$154") (pintype "bidirectional"))
      (node (ref "CN2") (pin "P$154") (pinfunction "PIXELCLK_P$154") (pintype "bidirectional"))
    )
    (net (code "99") (name "/RED") (class "Default")
      (node (ref "R5") (pin "2") (pinfunction "2_2") (pintype "passive"))
      (node (ref "X1") (pin "1") (pinfunction "F_1") (pintype "passive"))
    )
    (net (code "100") (name "/RIGHT") (class "Default")
      (node (ref "CN1") (pin "P$182") (pinfunction "RIGHT_P$182") (pintype "bidirectional"))
      (node (ref "CN2") (pin "P$182") (pinfunction "RIGHT_P$182") (pintype "bidirectional"))
    )
    (net (code "101") (name "/RIGHT_EXT") (class "Default")
      (node (ref "CN1") (pin "P$181") (pinfunction "RIGHT_EXT_P$181") (pintype "bidirectional"))
      (node (ref "CN2") (pin "P$181") (pinfunction "RIGHT_EXT_P$181") (pintype "bidirectional"))
    )
    (net (code "102") (name "/RS232_RX") (class "Default")
      (node (ref "IC1") (pin "6") (pinfunction "RIN_6") (pintype "input"))
      (node (ref "JP2") (pin "2") (pinfunction "2_2") (pintype "passive"))
    )
    (net (code "103") (name "/RS232_TX") (class "Default")
      (node (ref "IC1") (pin "7") (pinfunction "TOUT_7") (pintype "output"))
      (node (ref "JP2") (pin "1") (pinfunction "1_1") (pintype "passive"))
    )
    (net (code "104") (name "/R_W") (class "Default")
      (node (ref "CN1") (pin "P$93") (pinfunction "R_W_P$93") (pintype "bidirectional"))
      (node (ref "CN2") (pin "P$93") (pinfunction "R_W_P$93") (pintype "bidirectional"))
    )
    (net (code "105") (name "/SIZ0") (class "Default")
      (node (ref "CN1") (pin "P$88") (pinfunction "SIZE_0_P$88") (pintype "bidirectional"))
      (node (ref "CN2") (pin "P$88") (pinfunction "SIZE_0_P$88") (pintype "bidirectional"))
    )
    (net (code "106") (name "/SIZ1") (class "Default")
      (node (ref "CN1") (pin "P$87") (pinfunction "SIZE_1_P$87") (pintype "bidirectional"))
      (node (ref "CN2") (pin "P$87") (pinfunction "SIZE_1_P$87") (pintype "bidirectional"))
    )
    (net (code "107") (name "/VGND") (class "Default")
      (node (ref "CN1") (pin "P$161") (pinfunction "VGND_P$161") (pintype "bidirectional"))
      (node (ref "CN1") (pin "P$162") (pinfunction "VGND_P$162") (pintype "bidirectional"))
      (node (ref "CN1") (pin "P$170") (pinfunction "VGND_P$170") (pintype "bidirectional"))
      (node (ref "CN2") (pin "P$169") (pinfunction "VGND_P$169") (pintype "bidirectional"))
      (node (ref "CN2") (pin "P$170") (pinfunction "VGND_P$170") (pintype "bidirectional"))
    )
    (net (code "108") (name "/VGND@1") (class "Default")
      (node (ref "CN2") (pin "P$161") (pinfunction "VGND_P$161") (pintype "bidirectional"))
    )
    (net (code "109") (name "/VGND@2") (class "Default")
      (node (ref "CN2") (pin "P$162") (pinfunction "VGND_P$162") (pintype "bidirectional"))
    )
    (net (code "110") (name "/VGND@3") (class "Default")
      (node (ref "CN1") (pin "P$169") (pinfunction "VGND_P$169") (pintype "bidirectional"))
    )
    (net (code "111") (name "/VSYNC_3V3") (class "Default")
      (node (ref "R2") (pin "2") (pinfunction "2_2") (pintype "passive"))
      (node (ref "X1") (pin "14") (pinfunction "F_14") (pintype "passive"))
    )
    (net (code "112") (name "/XCLK") (class "Default")
      (node (ref "CN1") (pin "P$173") (pinfunction "XCLK_P$173") (pintype "bidirectional"))
      (node (ref "CN2") (pin "P$173") (pinfunction "XCLK_P$173") (pintype "bidirectional"))
    )
    (net (code "113") (name "/_ACTIVE") (class "Default")
      (node (ref "CN1") (pin "P$126") (pinfunction "_ACTIVE_P$126") (pintype "bidirectional"))
      (node (ref "CN2") (pin "P$126") (pinfunction "_ACTIVE_P$126") (pintype "bidirectional"))
    )
    (net (code "114") (name "/_AS") (class "Default")
      (node (ref "CN1") (pin "P$91") (pinfunction "_AS_P$91") (pintype "bidirectional"))
      (node (ref "CN2") (pin "P$91") (pinfunction "_AS_P$91") (pintype "bidirectional"))
    )
    (net (code "115") (name "/_AVEC") (class "Default")
      (node (ref "CN1") (pin "P$96") (pinfunction "_AVEC_P$96") (pintype "bidirectional"))
      (node (ref "CN2") (pin "P$96") (pinfunction "_AVEC_P$96") (pintype "bidirectional"))
    )
    (net (code "116") (name "/_BEER") (class "Default")
      (node (ref "CN1") (pin "P$94") (pinfunction "_BEER_P$94") (pintype "bidirectional"))
      (node (ref "CN2") (pin "P$94") (pinfunction "_BEER_P$94") (pintype "bidirectional"))
    )
    (net (code "117") (name "/_BLANK") (class "Default")
      (node (ref "CN1") (pin "P$153") (pinfunction "_BLANK_P$153") (pintype "bidirectional"))
      (node (ref "CN2") (pin "P$153") (pinfunction "_BLANK_P$153") (pintype "bidirectional"))
    )
    (net (code "118") (name "/_CPU_BG") (class "Default")
      (node (ref "CN1") (pin "P$113") (pinfunction "_CPU_BG_P$113") (pintype "bidirectional"))
      (node (ref "CN2") (pin "P$113") (pinfunction "_CPU_BG_P$113") (pintype "bidirectional"))
    )
    (net (code "119") (name "/_CPU_BR") (class "Default")
      (node (ref "CN1") (pin "P$111") (pinfunction "_CPU_BR_P$111") (pintype "bidirectional"))
      (node (ref "CN2") (pin "P$111") (pinfunction "_CPU_BR_P$111") (pintype "bidirectional"))
    )
    (net (code "120") (name "/_CSYNC") (class "Default")
      (node (ref "CN1") (pin "P$157") (pinfunction "_CSYNC_P$157") (pintype "bidirectional"))
      (node (ref "CN2") (pin "P$157") (pinfunction "_CSYNC_P$157") (pintype "bidirectional"))
      (node (ref "U1") (pin "1") (pinfunction "IN1_1") (pintype "input"))
    )
    (net (code "121") (name "/_DKRD") (class "Default")
      (node (ref "CN1") (pin "P$129") (pinfunction "_DKRD_P$129") (pintype "bidirectional"))
      (node (ref "CN2") (pin "P$129") (pinfunction "_DKRD_P$129") (pintype "bidirectional"))
    )
    (net (code "122") (name "/_DKWD") (class "Default")
      (node (ref "CN1") (pin "P$130") (pinfunction "_DKWD_P$130") (pintype "bidirectional"))
      (node (ref "CN2") (pin "P$130") (pinfunction "_DKWD_P$130") (pintype "bidirectional"))
    )
    (net (code "123") (name "/_DS") (class "Default")
      (node (ref "CN1") (pin "P$92") (pinfunction "_DS_P$92") (pintype "bidirectional"))
      (node (ref "CN2") (pin "P$92") (pinfunction "_DS_P$92") (pintype "bidirectional"))
    )
    (net (code "124") (name "/_DSACK_0") (class "Default")
      (node (ref "CN1") (pin "P$98") (pinfunction "_DSACK_0_P$98") (pintype "bidirectional"))
      (node (ref "CN2") (pin "P$98") (pinfunction "_DSACK_0_P$98") (pintype "bidirectional"))
    )
    (net (code "125") (name "/_DSACK_1") (class "Default")
      (node (ref "CN1") (pin "P$97") (pinfunction "_DSACK_1_P$97") (pintype "bidirectional"))
      (node (ref "CN2") (pin "P$97") (pinfunction "_DSACK_1_P$97") (pintype "bidirectional"))
    )
    (net (code "126") (name "/_EXP_BG") (class "Default")
      (node (ref "CN1") (pin "P$112") (pinfunction "_EXP_BG_P$112") (pintype "bidirectional"))
      (node (ref "CN2") (pin "P$112") (pinfunction "_EXP_BG_P$112") (pintype "bidirectional"))
    )
    (net (code "127") (name "/_EXP_BR") (class "Default")
      (node (ref "CN1") (pin "P$114") (pinfunction "_EXP_BR_P$114") (pintype "bidirectional"))
      (node (ref "CN2") (pin "P$114") (pinfunction "_EXP_BR_P$114") (pintype "bidirectional"))
    )
    (net (code "128") (name "/_EXT_AUDIO") (class "Default")
      (node (ref "CN1") (pin "P$140") (pinfunction "_EXT_AUDIO_P$140") (pintype "bidirectional"))
      (node (ref "CN2") (pin "P$140") (pinfunction "_EXT_AUDIO_P$140") (pintype "bidirectional"))
    )
    (net (code "129") (name "/_EXT_VIDEO") (class "Default")
      (node (ref "CN1") (pin "P$174") (pinfunction "_EXT_VIDEO_P$174") (pintype "bidirectional"))
      (node (ref "CN2") (pin "P$174") (pinfunction "_EXT_VIDEO_P$174") (pintype "bidirectional"))
    )
    (net (code "130") (name "/_FIRE0") (class "Default")
      (node (ref "CN1") (pin "P$123") (pinfunction "_FIRE0_P$123") (pintype "bidirectional"))
      (node (ref "CN2") (pin "P$123") (pinfunction "_FIRE0_P$123") (pintype "bidirectional"))
    )
    (net (code "131") (name "/_FIRE1") (class "Default")
      (node (ref "CN1") (pin "P$124") (pinfunction "_FIRE1_P$124") (pintype "bidirectional"))
      (node (ref "CN2") (pin "P$124") (pinfunction "_FIRE1_P$124") (pintype "bidirectional"))
    )
    (net (code "132") (name "/_HLT") (class "Default")
      (node (ref "CN1") (pin "P$86") (pinfunction "_HLT_P$86") (pintype "bidirectional"))
      (node (ref "CN2") (pin "P$86") (pinfunction "_HLT_P$86") (pintype "bidirectional"))
    )
    (net (code "133") (name "/_HSYNC") (class "Default")
      (node (ref "CN1") (pin "P$159") (pinfunction "_HSYNC_P$159") (pintype "bidirectional"))
      (node (ref "CN2") (pin "P$159") (pinfunction "_HSYNC_P$159") (pintype "bidirectional"))
      (node (ref "U1") (pin "3") (pinfunction "IN0_3") (pintype "input"))
    )
    (net (code "134") (name "/_INT2") (class "Default")
      (node (ref "CN1") (pin "P$119") (pinfunction "_INT2_P$119") (pintype "bidirectional"))
      (node (ref "CN2") (pin "P$119") (pinfunction "_INT2_P$119") (pintype "bidirectional"))
    )
    (net (code "135") (name "/_INT6") (class "Default")
      (node (ref "CN1") (pin "P$120") (pinfunction "_INT6_P$120") (pintype "bidirectional"))
      (node (ref "CN2") (pin "P$120") (pinfunction "_INT6_P$120") (pintype "bidirectional"))
    )
    (net (code "136") (name "/_KB_CLOCK") (class "Default")
      (node (ref "CN1") (pin "P$121") (pinfunction "_KB_CLOCK_P$121") (pintype "bidirectional"))
      (node (ref "CN2") (pin "P$121") (pinfunction "_KB_CLOCK_P$121") (pintype "bidirectional"))
      (node (ref "IC6") (pin "3") (pinfunction "RA4/TOCKI/CMP2_3") (pintype "bidirectional"))
    )
    (net (code "137") (name "/_KB_DATA") (class "Default")
      (node (ref "CN1") (pin "P$122") (pinfunction "_KB_DATA_P$122") (pintype "bidirectional"))
      (node (ref "CN2") (pin "P$122") (pinfunction "_KB_DATA_P$122") (pintype "bidirectional"))
      (node (ref "IC6") (pin "2") (pinfunction "RA3/AN3/CMP1_2") (pintype "bidirectional"))
    )
    (net (code "138") (name "/_LED") (class "Default")
      (node (ref "CN1") (pin "P$125") (pinfunction "_LED_P$125") (pintype "bidirectional"))
      (node (ref "CN2") (pin "P$125") (pinfunction "_LED_P$125") (pintype "bidirectional"))
    )
    (net (code "139") (name "/_MUTE") (class "Default")
      (node (ref "CN1") (pin "P$142") (pinfunction "_MUTE_P$142") (pintype "bidirectional"))
      (node (ref "CN2") (pin "P$142") (pinfunction "_MUTE_P$142") (pintype "bidirectional"))
    )
    (net (code "140") (name "/_NTSC") (class "Default")
      (node (ref "CN1") (pin "P$171") (pinfunction "_NTSC_P$171") (pintype "bidirectional"))
      (node (ref "CN2") (pin "P$171") (pinfunction "_NTSC_P$171") (pintype "bidirectional"))
    )
    (net (code "141") (name "/_PIXELSW") (class "Default")
      (node (ref "CN1") (pin "P$152") (pinfunction "_PIXELSW_P$152") (pintype "bidirectional"))
      (node (ref "CN2") (pin "P$152") (pinfunction "_PIXELSW_P$152") (pintype "bidirectional"))
    )
    (net (code "142") (name "/_PIXELSW_EXT") (class "Default")
      (node (ref "CN1") (pin "P$151") (pinfunction "_PIXELSW_EXT_P$151") (pintype "bidirectional"))
      (node (ref "CN2") (pin "P$151") (pinfunction "_PIXELSW_EXT_P$151") (pintype "bidirectional"))
    )
    (net (code "143") (name "/_PUNT") (class "Default")
      (node (ref "CN1") (pin "P$117") (pinfunction "_PUNT_P$117") (pintype "bidirectional"))
      (node (ref "CN2") (pin "P$117") (pinfunction "_PUNT_P$117") (pintype "bidirectional"))
    )
    (net (code "144") (name "/_RESET") (class "Default")
      (node (ref "CN1") (pin "P$118") (pinfunction "_RESET_P$118") (pintype "bidirectional"))
      (node (ref "CN2") (pin "P$118") (pinfunction "_RESET_P$118") (pintype "bidirectional"))
    )
    (net (code "145") (name "/_RMC") (class "Default")
      (node (ref "CN1") (pin "P$106") (pinfunction "_RMC_P$106") (pintype "bidirectional"))
      (node (ref "CN2") (pin "P$106") (pinfunction "_RMC_P$106") (pintype "bidirectional"))
    )
    (net (code "146") (name "/_RST") (class "Default")
      (node (ref "CN1") (pin "P$85") (pinfunction "_RST_P$85") (pintype "bidirectional"))
      (node (ref "CN2") (pin "P$85") (pinfunction "_RST_P$85") (pintype "bidirectional"))
    )
    (net (code "147") (name "/_RXD") (class "Default")
      (node (ref "CN1") (pin "P$127") (pinfunction "_RXD_P$127") (pintype "bidirectional"))
      (node (ref "CN2") (pin "P$127") (pinfunction "_RXD_P$127") (pintype "bidirectional"))
      (node (ref "IC1") (pin "5") (pinfunction "ROUT_5") (pintype "output"))
      (node (ref "JP2") (pin "5") (pinfunction "5_5") (pintype "passive"))
    )
    (net (code "148") (name "/_TXD") (class "Default")
      (node (ref "CN1") (pin "P$128") (pinfunction "_TXD_P$128") (pintype "bidirectional"))
      (node (ref "CN2") (pin "P$128") (pinfunction "_TXD_P$128") (pintype "bidirectional"))
      (node (ref "IC1") (pin "4") (pinfunction "TIN_4") (pintype "input"))
      (node (ref "JP2") (pin "4") (pinfunction "4_4") (pintype "passive"))
    )
    (net (code "149") (name "/_VSYNC") (class "Default")
      (node (ref "CN1") (pin "P$160") (pinfunction "_VSYNC_P$160") (pintype "bidirectional"))
      (node (ref "CN2") (pin "P$160") (pinfunction "_VSYNC_P$160") (pintype "bidirectional"))
      (node (ref "U2") (pin "3") (pinfunction "IN0_3") (pintype "input"))
    )
    (net (code "150") (name "/_XCLKEN") (class "Default")
      (node (ref "CN1") (pin "P$172") (pinfunction "_XCLKEN_P$172") (pintype "bidirectional"))
      (node (ref "CN2") (pin "P$172") (pinfunction "_XCLKEN_P$172") (pintype "bidirectional"))
    )
    (net (code "151") (name "/~{MCLR}") (class "Default")
      (node (ref "IC6") (pin "4") (pinfunction "RA5/MCLR/VPP_4") (pintype "bidirectional"))
      (node (ref "J2") (pin "6") (pinfunction "VPP_6") (pintype "bidirectional"))
    )
    (net (code "152") (name "GND") (class "Default")
      (node (ref "C10") (pin "-") (pinfunction "-_-") (pintype "passive"))
      (node (ref "C11") (pin "2") (pinfunction "2_2") (pintype "passive"))
      (node (ref "C13") (pin "2") (pinfunction "2_2") (pintype "passive"))
      (node (ref "C14") (pin "2") (pinfunction "2_2") (pintype "passive"))
      (node (ref "C16") (pin "2") (pinfunction "2_2") (pintype "passive"))
      (node (ref "C17") (pin "2") (pinfunction "2_2") (pintype "passive"))
      (node (ref "C2") (pin "2") (pinfunction "2_2") (pintype "passive"))
      (node (ref "C3") (pin "2") (pinfunction "2_2") (pintype "passive"))
      (node (ref "C4") (pin "2") (pinfunction "2_2") (pintype "passive"))
      (node (ref "C5") (pin "-") (pinfunction "-_-") (pintype "passive"))
      (node (ref "C6") (pin "2") (pinfunction "2_2") (pintype "passive"))
      (node (ref "C7") (pin "2") (pinfunction "2_2") (pintype "passive"))
      (node (ref "C9") (pin "-") (pinfunction "-_-") (pintype "passive"))
      (node (ref "CN1") (pin "P$101") (pinfunction "GND_P$101") (pintype "bidirectional"))
      (node (ref "CN1") (pin "P$131") (pinfunction "GND_P$131") (pintype "bidirectional"))
      (node (ref "CN1") (pin "P$133") (pinfunction "GND_P$133") (pintype "bidirectional"))
      (node (ref "CN1") (pin "P$135") (pinfunction "GND_P$135") (pintype "bidirectional"))
      (node (ref "CN1") (pin "P$137") (pinfunction "GND_P$137") (pintype "bidirectional"))
      (node (ref "CN1") (pin "P$145") (pinfunction "GND_P$145") (pintype "bidirectional"))
      (node (ref "CN1") (pin "P$155") (pinfunction "GND_P$155") (pintype "bidirectional"))
      (node (ref "CN1") (pin "P$175") (pinfunction "GND_P$175") (pintype "bidirectional"))
      (node (ref "CN1") (pin "P$19") (pinfunction "GND_P$19") (pintype "bidirectional"))
      (node (ref "CN1") (pin "P$29") (pinfunction "GND_P$29") (pintype "bidirectional"))
      (node (ref "CN1") (pin "P$39") (pinfunction "GND_P$39") (pintype "bidirectional"))
      (node (ref "CN1") (pin "P$49") (pinfunction "GND_P$49") (pintype "bidirectional"))
      (node (ref "CN1") (pin "P$59") (pinfunction "GND_P$59") (pintype "bidirectional"))
      (node (ref "CN1") (pin "P$69") (pinfunction "GND_P$69") (pintype "bidirectional"))
      (node (ref "CN1") (pin "P$79") (pinfunction "GND_P$79") (pintype "bidirectional"))
      (node (ref "CN1") (pin "P$9") (pinfunction "GND_P$9") (pintype "bidirectional"))
      (node (ref "CN2") (pin "P$101") (pinfunction "GND_P$101") (pintype "bidirectional"))
      (node (ref "CN2") (pin "P$131") (pinfunction "GND_P$131") (pintype "bidirectional"))
      (node (ref "CN2") (pin "P$133") (pinfunction "GND_P$133") (pintype "bidirectional"))
      (node (ref "CN2") (pin "P$135") (pinfunction "GND_P$135") (pintype "bidirectional"))
      (node (ref "CN2") (pin "P$137") (pinfunction "GND_P$137") (pintype "bidirectional"))
      (node (ref "CN2") (pin "P$145") (pinfunction "GND_P$145") (pintype "bidirectional"))
      (node (ref "CN2") (pin "P$155") (pinfunction "GND_P$155") (pintype "bidirectional"))
      (node (ref "CN2") (pin "P$175") (pinfunction "GND_P$175") (pintype "bidirectional"))
      (node (ref "CN2") (pin "P$19") (pinfunction "GND_P$19") (pintype "bidirectional"))
      (node (ref "CN2") (pin "P$29") (pinfunction "GND_P$29") (pintype "bidirectional"))
      (node (ref "CN2") (pin "P$39") (pinfunction "GND_P$39") (pintype "bidirectional"))
      (node (ref "CN2") (pin "P$49") (pinfunction "GND_P$49") (pintype "bidirectional"))
      (node (ref "CN2") (pin "P$59") (pinfunction "GND_P$59") (pintype "bidirectional"))
      (node (ref "CN2") (pin "P$69") (pinfunction "GND_P$69") (pintype "bidirectional"))
      (node (ref "CN2") (pin "P$79") (pinfunction "GND_P$79") (pintype "bidirectional"))
      (node (ref "CN2") (pin "P$9") (pinfunction "GND_P$9") (pintype "bidirectional"))
      (node (ref "IC1") (pin "10") (pinfunction "GND_10") (pintype "power_in"))
      (node (ref "IC5") (pin "1") (pinfunction "ADJ_1") (pintype "input"))
      (node (ref "IC6") (pin "5") (pinfunction "VSS_5") (pintype "power_in"))
      (node (ref "J2") (pin "4") (pinfunction "GND_4") (pintype "power_in"))
      (node (ref "JP1") (pin "1") (pinfunction "1_1") (pintype "passive"))
      (node (ref "JP2") (pin "3") (pinfunction "3_3") (pintype "passive"))
      (node (ref "U1") (pin "2") (pinfunction "GND_2") (pintype "passive"))
      (node (ref "U2") (pin "2") (pinfunction "GND_2") (pintype "passive"))
      (node (ref "X1") (pin "10") (pinfunction "F_10") (pintype "passive"))
      (node (ref "X1") (pin "5") (pinfunction "F_5") (pintype "passive"))
      (node (ref "X1") (pin "6") (pinfunction "F_6") (pintype "passive"))
      (node (ref "X1") (pin "7") (pinfunction "F_7") (pintype "passive"))
      (node (ref "X1") (pin "8") (pinfunction "F_8") (pintype "passive"))
      (node (ref "X2") (pin "3") (pinfunction "3_3") (pintype "passive"))
    )
    (net (code "153") (name "Net-(IC1-C1+)") (class "Default")
      (node (ref "C1") (pin "1") (pinfunction "1_1") (pintype "passive"))
      (node (ref "IC1") (pin "9") (pinfunction "C1+_9") (pintype "passive"))
    )
    (net (code "154") (name "Net-(IC1-C1-)") (class "Default")
      (node (ref "C1") (pin "2") (pinfunction "2_2") (pintype "passive"))
      (node (ref "IC1") (pin "2") (pinfunction "C1-_2") (pintype "passive"))
    )
    (net (code "155") (name "Net-(IC1-V-)") (class "Default")
      (node (ref "C2") (pin "1") (pinfunction "1_1") (pintype "passive"))
      (node (ref "IC1") (pin "8") (pinfunction "V-_8") (pintype "passive"))
    )
    (net (code "156") (name "Net-(IC6-RA7{slash}OSC1{slash}CLKIN)") (class "Default")
      (node (ref "C17") (pin "1") (pinfunction "1_1") (pintype "passive"))
      (node (ref "IC6") (pin "16") (pinfunction "RA7/OSC1/CLKIN_16") (pintype "bidirectional"))
      (node (ref "R8") (pin "1") (pinfunction "1_1") (pintype "passive"))
    )
    (net (code "157") (name "Net-(U1-IN2)") (class "Default")
      (node (ref "JP1") (pin "2") (pinfunction "2_2") (pintype "passive"))
      (node (ref "R4") (pin "1") (pinfunction "1_1") (pintype "passive"))
      (node (ref "U1") (pin "6") (pinfunction "IN2_6") (pintype "input"))
      (node (ref "U2") (pin "6") (pinfunction "IN2_6") (pintype "input"))
    )
    (net (code "158") (name "Net-(U1-Y)") (class "Default")
      (node (ref "R1") (pin "1") (pinfunction "1_1") (pintype "passive"))
      (node (ref "U1") (pin "4") (pinfunction "Y_4") (pintype "output"))
    )
    (net (code "159") (name "Net-(U2-IN1)") (class "Default")
      (node (ref "R3") (pin "1") (pinfunction "1_1") (pintype "passive"))
      (node (ref "U2") (pin "1") (pinfunction "IN1_1") (pintype "input"))
    )
    (net (code "160") (name "Net-(U2-Y)") (class "Default")
      (node (ref "R2") (pin "1") (pinfunction "1_1") (pintype "passive"))
      (node (ref "U2") (pin "4") (pinfunction "Y_4") (pintype "output"))
    )
    (net (code "161") (name "VCC") (class "Default")
      (node (ref "C10") (pin "+") (pinfunction "+_+") (pintype "passive"))
      (node (ref "C11") (pin "1") (pinfunction "1_1") (pintype "passive"))
      (node (ref "C13") (pin "1") (pinfunction "1_1") (pintype "passive"))
      (node (ref "C14") (pin "1") (pinfunction "1_1") (pintype "passive"))
      (node (ref "C16") (pin "1") (pinfunction "1_1") (pintype "passive"))
      (node (ref "C3") (pin "1") (pinfunction "1_1") (pintype "passive"))
      (node (ref "C4") (pin "1") (pinfunction "1_1") (pintype "passive"))
      (node (ref "C9") (pin "+") (pinfunction "+_+") (pintype "passive"))
      (node (ref "CN1") (pin "P$10") (pinfunction "VCC_P$10") (pintype "bidirectional"))
      (node (ref "CN1") (pin "P$102") (pinfunction "VCC_P$102") (pintype "bidirectional"))
      (node (ref "CN1") (pin "P$146") (pinfunction "VCC_P$146") (pintype "bidirectional"))
      (node (ref "CN1") (pin "P$156") (pinfunction "VCC_P$156") (pintype "bidirectional"))
      (node (ref "CN1") (pin "P$176") (pinfunction "VCC_P$176") (pintype "bidirectional"))
      (node (ref "CN1") (pin "P$20") (pinfunction "VCC_P$20") (pintype "bidirectional"))
      (node (ref "CN1") (pin "P$30") (pinfunction "VCC_P$30") (pintype "bidirectional"))
      (node (ref "CN1") (pin "P$40") (pinfunction "VCC_P$40") (pintype "bidirectional"))
      (node (ref "CN1") (pin "P$50") (pinfunction "VCC_P$50") (pintype "bidirectional"))
      (node (ref "CN1") (pin "P$60") (pinfunction "VCC_P$60") (pintype "bidirectional"))
      (node (ref "CN1") (pin "P$70") (pinfunction "VCC_P$70") (pintype "bidirectional"))
      (node (ref "CN1") (pin "P$80") (pinfunction "VCC_P$80") (pintype "bidirectional"))
      (node (ref "CN2") (pin "P$10") (pinfunction "VCC_P$10") (pintype "bidirectional"))
      (node (ref "CN2") (pin "P$102") (pinfunction "VCC_P$102") (pintype "bidirectional"))
      (node (ref "CN2") (pin "P$146") (pinfunction "VCC_P$146") (pintype "bidirectional"))
      (node (ref "CN2") (pin "P$156") (pinfunction "VCC_P$156") (pintype "bidirectional"))
      (node (ref "CN2") (pin "P$176") (pinfunction "VCC_P$176") (pintype "bidirectional"))
      (node (ref "CN2") (pin "P$20") (pinfunction "VCC_P$20") (pintype "bidirectional"))
      (node (ref "CN2") (pin "P$30") (pinfunction "VCC_P$30") (pintype "bidirectional"))
      (node (ref "CN2") (pin "P$40") (pinfunction "VCC_P$40") (pintype "bidirectional"))
      (node (ref "CN2") (pin "P$50") (pinfunction "VCC_P$50") (pintype "bidirectional"))
      (node (ref "CN2") (pin "P$60") (pinfunction "VCC_P$60") (pintype "bidirectional"))
      (node (ref "CN2") (pin "P$70") (pinfunction "VCC_P$70") (pintype "bidirectional"))
      (node (ref "CN2") (pin "P$80") (pinfunction "VCC_P$80") (pintype "bidirectional"))
      (node (ref "IC1") (pin "1") (pinfunction "VCC_1") (pintype "power_in"))
      (node (ref "IC1") (pin "3") (pinfunction "~{SHDN}_3") (pintype "input"))
      (node (ref "IC5") (pin "3") (pinfunction "IN_3") (pintype "input"))
      (node (ref "IC6") (pin "14") (pinfunction "VDD_14") (pintype "power_in"))
      (node (ref "J2") (pin "5") (pinfunction "VCC_5") (pintype "power_in"))
      (node (ref "R8") (pin "2") (pinfunction "2_2") (pintype "passive"))
      (node (ref "X2") (pin "4") (pinfunction "4_4") (pintype "passive"))
    )
    (net (code "162") (name "unconnected-(CN1-17MHZ-PadP$139)") (class "Default")
      (node (ref "CN1") (pin "P$139") (pinfunction "17MHZ_P$139") (pintype "bidirectional"))
    )
    (net (code "163") (name "unconnected-(CN1-DA_BCLK-PadP$144)") (class "Default")
      (node (ref "CN1") (pin "P$144") (pinfunction "DA_BCLK_P$144") (pintype "bidirectional"))
    )
    (net (code "164") (name "unconnected-(CN1-DA_DATA-PadP$141)") (class "Default")
      (node (ref "CN1") (pin "P$141") (pinfunction "DA_DATA_P$141") (pintype "bidirectional"))
    )
    (net (code "165") (name "unconnected-(CN1-DA_LRCLK-PadP$143)") (class "Default")
      (node (ref "CN1") (pin "P$143") (pinfunction "DA_LRCLK_P$143") (pintype "bidirectional"))
    )
    (net (code "166") (name "unconnected-(CN1-NC-PadP$89)") (class "Default")
      (node (ref "CN1") (pin "P$89") (pinfunction "NC_P$89") (pintype "bidirectional"))
    )
    (net (code "167") (name "unconnected-(CN1-NC-PadP$90)") (class "Default")
      (node (ref "CN1") (pin "P$90") (pinfunction "NC_P$90") (pintype "bidirectional"))
    )
    (net (code "168") (name "unconnected-(CN1-NC-PadP$95)") (class "Default")
      (node (ref "CN1") (pin "P$95") (pinfunction "NC_P$95") (pintype "bidirectional"))
    )
    (net (code "169") (name "unconnected-(CN1-NC-PadP$100)") (class "Default")
      (node (ref "CN1") (pin "P$100") (pinfunction "NC_P$100") (pintype "bidirectional"))
    )
    (net (code "170") (name "unconnected-(CN1-NC-PadP$107)") (class "Default")
      (node (ref "CN1") (pin "P$107") (pinfunction "NC_P$107") (pintype "bidirectional"))
    )
    (net (code "171") (name "unconnected-(CN1-NC-PadP$108)") (class "Default")
      (node (ref "CN1") (pin "P$108") (pinfunction "NC_P$108") (pintype "bidirectional"))
    )
    (net (code "172") (name "unconnected-(CN1-NC-PadP$109)") (class "Default")
      (node (ref "CN1") (pin "P$109") (pinfunction "NC_P$109") (pintype "bidirectional"))
    )
    (net (code "173") (name "unconnected-(CN1-NC-PadP$110)") (class "Default")
      (node (ref "CN1") (pin "P$110") (pinfunction "NC_P$110") (pintype "bidirectional"))
    )
    (net (code "174") (name "unconnected-(CN1-NC-PadP$115)") (class "Default")
      (node (ref "CN1") (pin "P$115") (pinfunction "NC_P$115") (pintype "bidirectional"))
    )
    (net (code "175") (name "unconnected-(CN1-NC-PadP$116)") (class "Default")
      (node (ref "CN1") (pin "P$116") (pinfunction "NC_P$116") (pintype "bidirectional"))
    )
    (net (code "176") (name "unconnected-(CN1-NC-PadP$134)") (class "Default")
      (node (ref "CN1") (pin "P$134") (pinfunction "NC_P$134") (pintype "bidirectional"))
    )
    (net (code "177") (name "unconnected-(CN2-17MHZ-PadP$139)") (class "Default")
      (node (ref "CN2") (pin "P$139") (pinfunction "17MHZ_P$139") (pintype "bidirectional"))
    )
    (net (code "178") (name "unconnected-(CN2-DA_BCLK-PadP$144)") (class "Default")
      (node (ref "CN2") (pin "P$144") (pinfunction "DA_BCLK_P$144") (pintype "bidirectional"))
    )
    (net (code "179") (name "unconnected-(CN2-DA_DATA-PadP$141)") (class "Default")
      (node (ref "CN2") (pin "P$141") (pinfunction "DA_DATA_P$141") (pintype "bidirectional"))
    )
    (net (code "180") (name "unconnected-(CN2-DA_LRCLK-PadP$143)") (class "Default")
      (node (ref "CN2") (pin "P$143") (pinfunction "DA_LRCLK_P$143") (pintype "bidirectional"))
    )
    (net (code "181") (name "unconnected-(CN2-NC-PadP$84)") (class "Default")
      (node (ref "CN2") (pin "P$84") (pinfunction "NC_P$84") (pintype "bidirectional"))
    )
    (net (code "182") (name "unconnected-(CN2-NC-PadP$89)") (class "Default")
      (node (ref "CN2") (pin "P$89") (pinfunction "NC_P$89") (pintype "bidirectional"))
    )
    (net (code "183") (name "unconnected-(CN2-NC-PadP$90)") (class "Default")
      (node (ref "CN2") (pin "P$90") (pinfunction "NC_P$90") (pintype "bidirectional"))
    )
    (net (code "184") (name "unconnected-(CN2-NC-PadP$95)") (class "Default")
      (node (ref "CN2") (pin "P$95") (pinfunction "NC_P$95") (pintype "bidirectional"))
    )
    (net (code "185") (name "unconnected-(CN2-NC-PadP$100)") (class "Default")
      (node (ref "CN2") (pin "P$100") (pinfunction "NC_P$100") (pintype "bidirectional"))
    )
    (net (code "186") (name "unconnected-(CN2-NC-PadP$107)") (class "Default")
      (node (ref "CN2") (pin "P$107") (pinfunction "NC_P$107") (pintype "bidirectional"))
    )
    (net (code "187") (name "unconnected-(CN2-NC-PadP$108)") (class "Default")
      (node (ref "CN2") (pin "P$108") (pinfunction "NC_P$108") (pintype "bidirectional"))
    )
    (net (code "188") (name "unconnected-(CN2-NC-PadP$109)") (class "Default")
      (node (ref "CN2") (pin "P$109") (pinfunction "NC_P$109") (pintype "bidirectional"))
    )
    (net (code "189") (name "unconnected-(CN2-NC-PadP$110)") (class "Default")
      (node (ref "CN2") (pin "P$110") (pinfunction "NC_P$110") (pintype "bidirectional"))
    )
    (net (code "190") (name "unconnected-(CN2-NC-PadP$115)") (class "Default")
      (node (ref "CN2") (pin "P$115") (pinfunction "NC_P$115") (pintype "bidirectional"))
    )
    (net (code "191") (name "unconnected-(CN2-NC-PadP$116)") (class "Default")
      (node (ref "CN2") (pin "P$116") (pinfunction "NC_P$116") (pintype "bidirectional"))
    )
    (net (code "192") (name "unconnected-(CN2-NC-PadP$134)") (class "Default")
      (node (ref "CN2") (pin "P$134") (pinfunction "NC_P$134") (pintype "bidirectional"))
    )
    (net (code "193") (name "unconnected-(IC6-RA0{slash}AN0-Pad17)") (class "Default")
      (node (ref "IC6") (pin "17") (pinfunction "RA0/AN0_17") (pintype "bidirectional"))
    )
    (net (code "194") (name "unconnected-(IC6-RA1{slash}AN1-Pad18)") (class "Default")
      (node (ref "IC6") (pin "18") (pinfunction "RA1/AN1_18") (pintype "bidirectional"))
    )
    (net (code "195") (name "unconnected-(IC6-RA2{slash}AN2{slash}VREF-Pad1)") (class "Default")
      (node (ref "IC6") (pin "1") (pinfunction "RA2/AN2/VREF_1") (pintype "bidirectional"))
    )
    (net (code "196") (name "unconnected-(IC6-RA6{slash}OSC2{slash}CLKOUT-Pad15)") (class "Default")
      (node (ref "IC6") (pin "15") (pinfunction "RA6/OSC2/CLKOUT_15") (pintype "bidirectional"))
    )
    (net (code "197") (name "unconnected-(IC6-RB2{slash}TX{slash}CK-Pad8)") (class "Default")
      (node (ref "IC6") (pin "8") (pinfunction "RB2/TX/CK_8") (pintype "bidirectional"))
    )
    (net (code "198") (name "unconnected-(IC6-RB3{slash}CCP1-Pad9)") (class "Default")
      (node (ref "IC6") (pin "9") (pinfunction "RB3/CCP1_9") (pintype "bidirectional"))
    )
    (net (code "199") (name "unconnected-(IC6-RB4{slash}PGM-Pad10)") (class "Default")
      (node (ref "IC6") (pin "10") (pinfunction "RB4/PGM_10") (pintype "bidirectional"))
    )
    (net (code "200") (name "unconnected-(IC6-RB5-Pad11)") (class "Default")
      (node (ref "IC6") (pin "11") (pinfunction "RB5_11") (pintype "bidirectional"))
    )
    (net (code "201") (name "unconnected-(J2-PGM-Pad1)") (class "Default")
      (node (ref "J2") (pin "1") (pinfunction "PGM_1") (pintype "bidirectional"))
    )
    (net (code "202") (name "unconnected-(X1C-F-Pad11)") (class "Default")
      (node (ref "X1") (pin "11") (pinfunction "F_11") (pintype "passive"))
    )
    (net (code "203") (name "unconnected-(X1D-F-Pad12)") (class "Default")
      (node (ref "X1") (pin "12") (pinfunction "F_12") (pintype "passive"))
    )
    (net (code "204") (name "unconnected-(X1G-F-Pad15)") (class "Default")
      (node (ref "X1") (pin "15") (pinfunction "F_15") (pintype "passive"))
    )
    (net (code "205") (name "unconnected-(X1J-F-Pad4)") (class "Default")
      (node (ref "X1") (pin "4") (pinfunction "F_4") (pintype "passive"))
    )
    (net (code "206") (name "unconnected-(X1O-F-Pad9)") (class "Default")
      (node (ref "X1") (pin "9") (pinfunction "F_9") (pintype "passive"))
    )
    (net (code "207") (name "unconnected-(X2-Pad2)") (class "Default")
      (node (ref "X2") (pin "2") (pinfunction "2_2") (pintype "passive"))
    )
    (net (code "208") (name "unconnected-(X2-Pad6)") (class "Default")
      (node (ref "X2") (pin "6") (pinfunction "6_6") (pintype "passive"))
    )
  )
)
